# 4th_main.net
KiCad netlist of a schematic drawn in Altium Designer
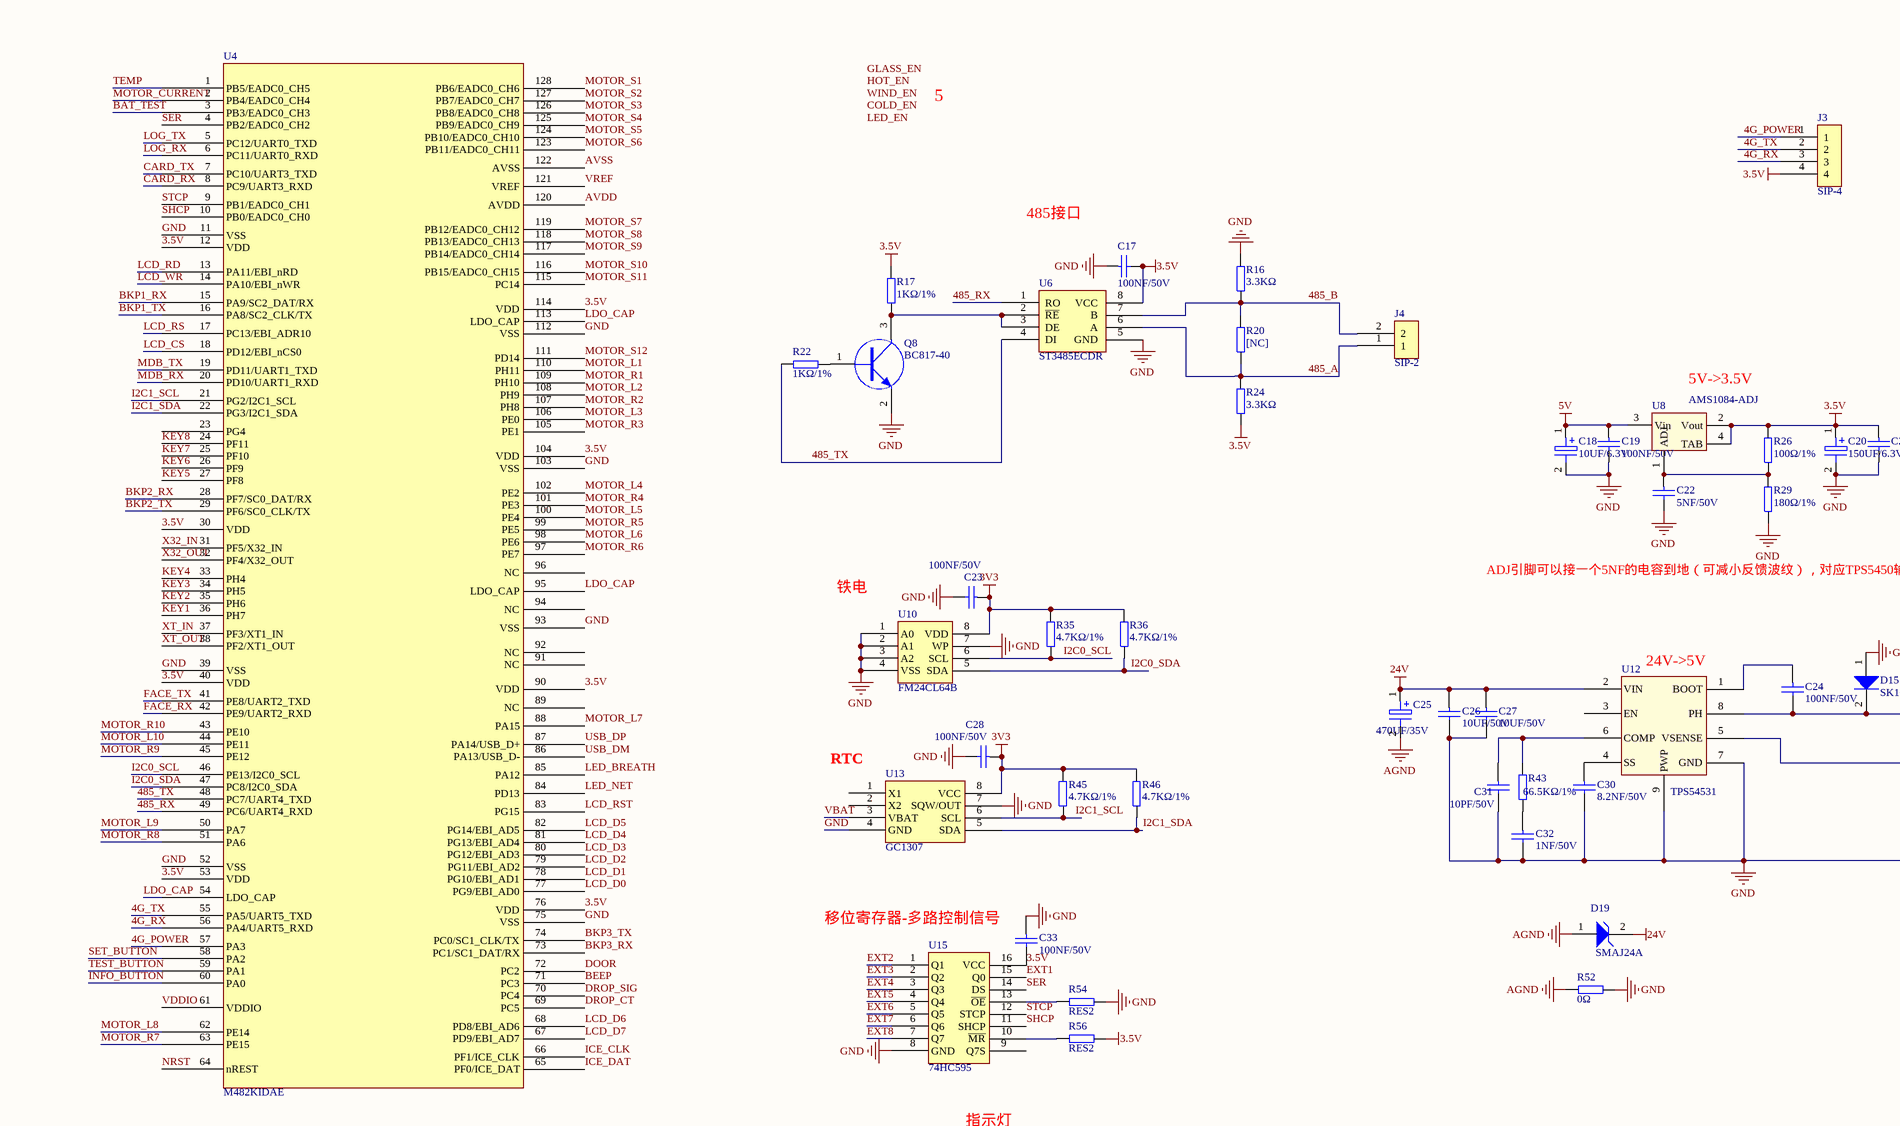
[diagram p0: 4th_main.SchDoc, top left]
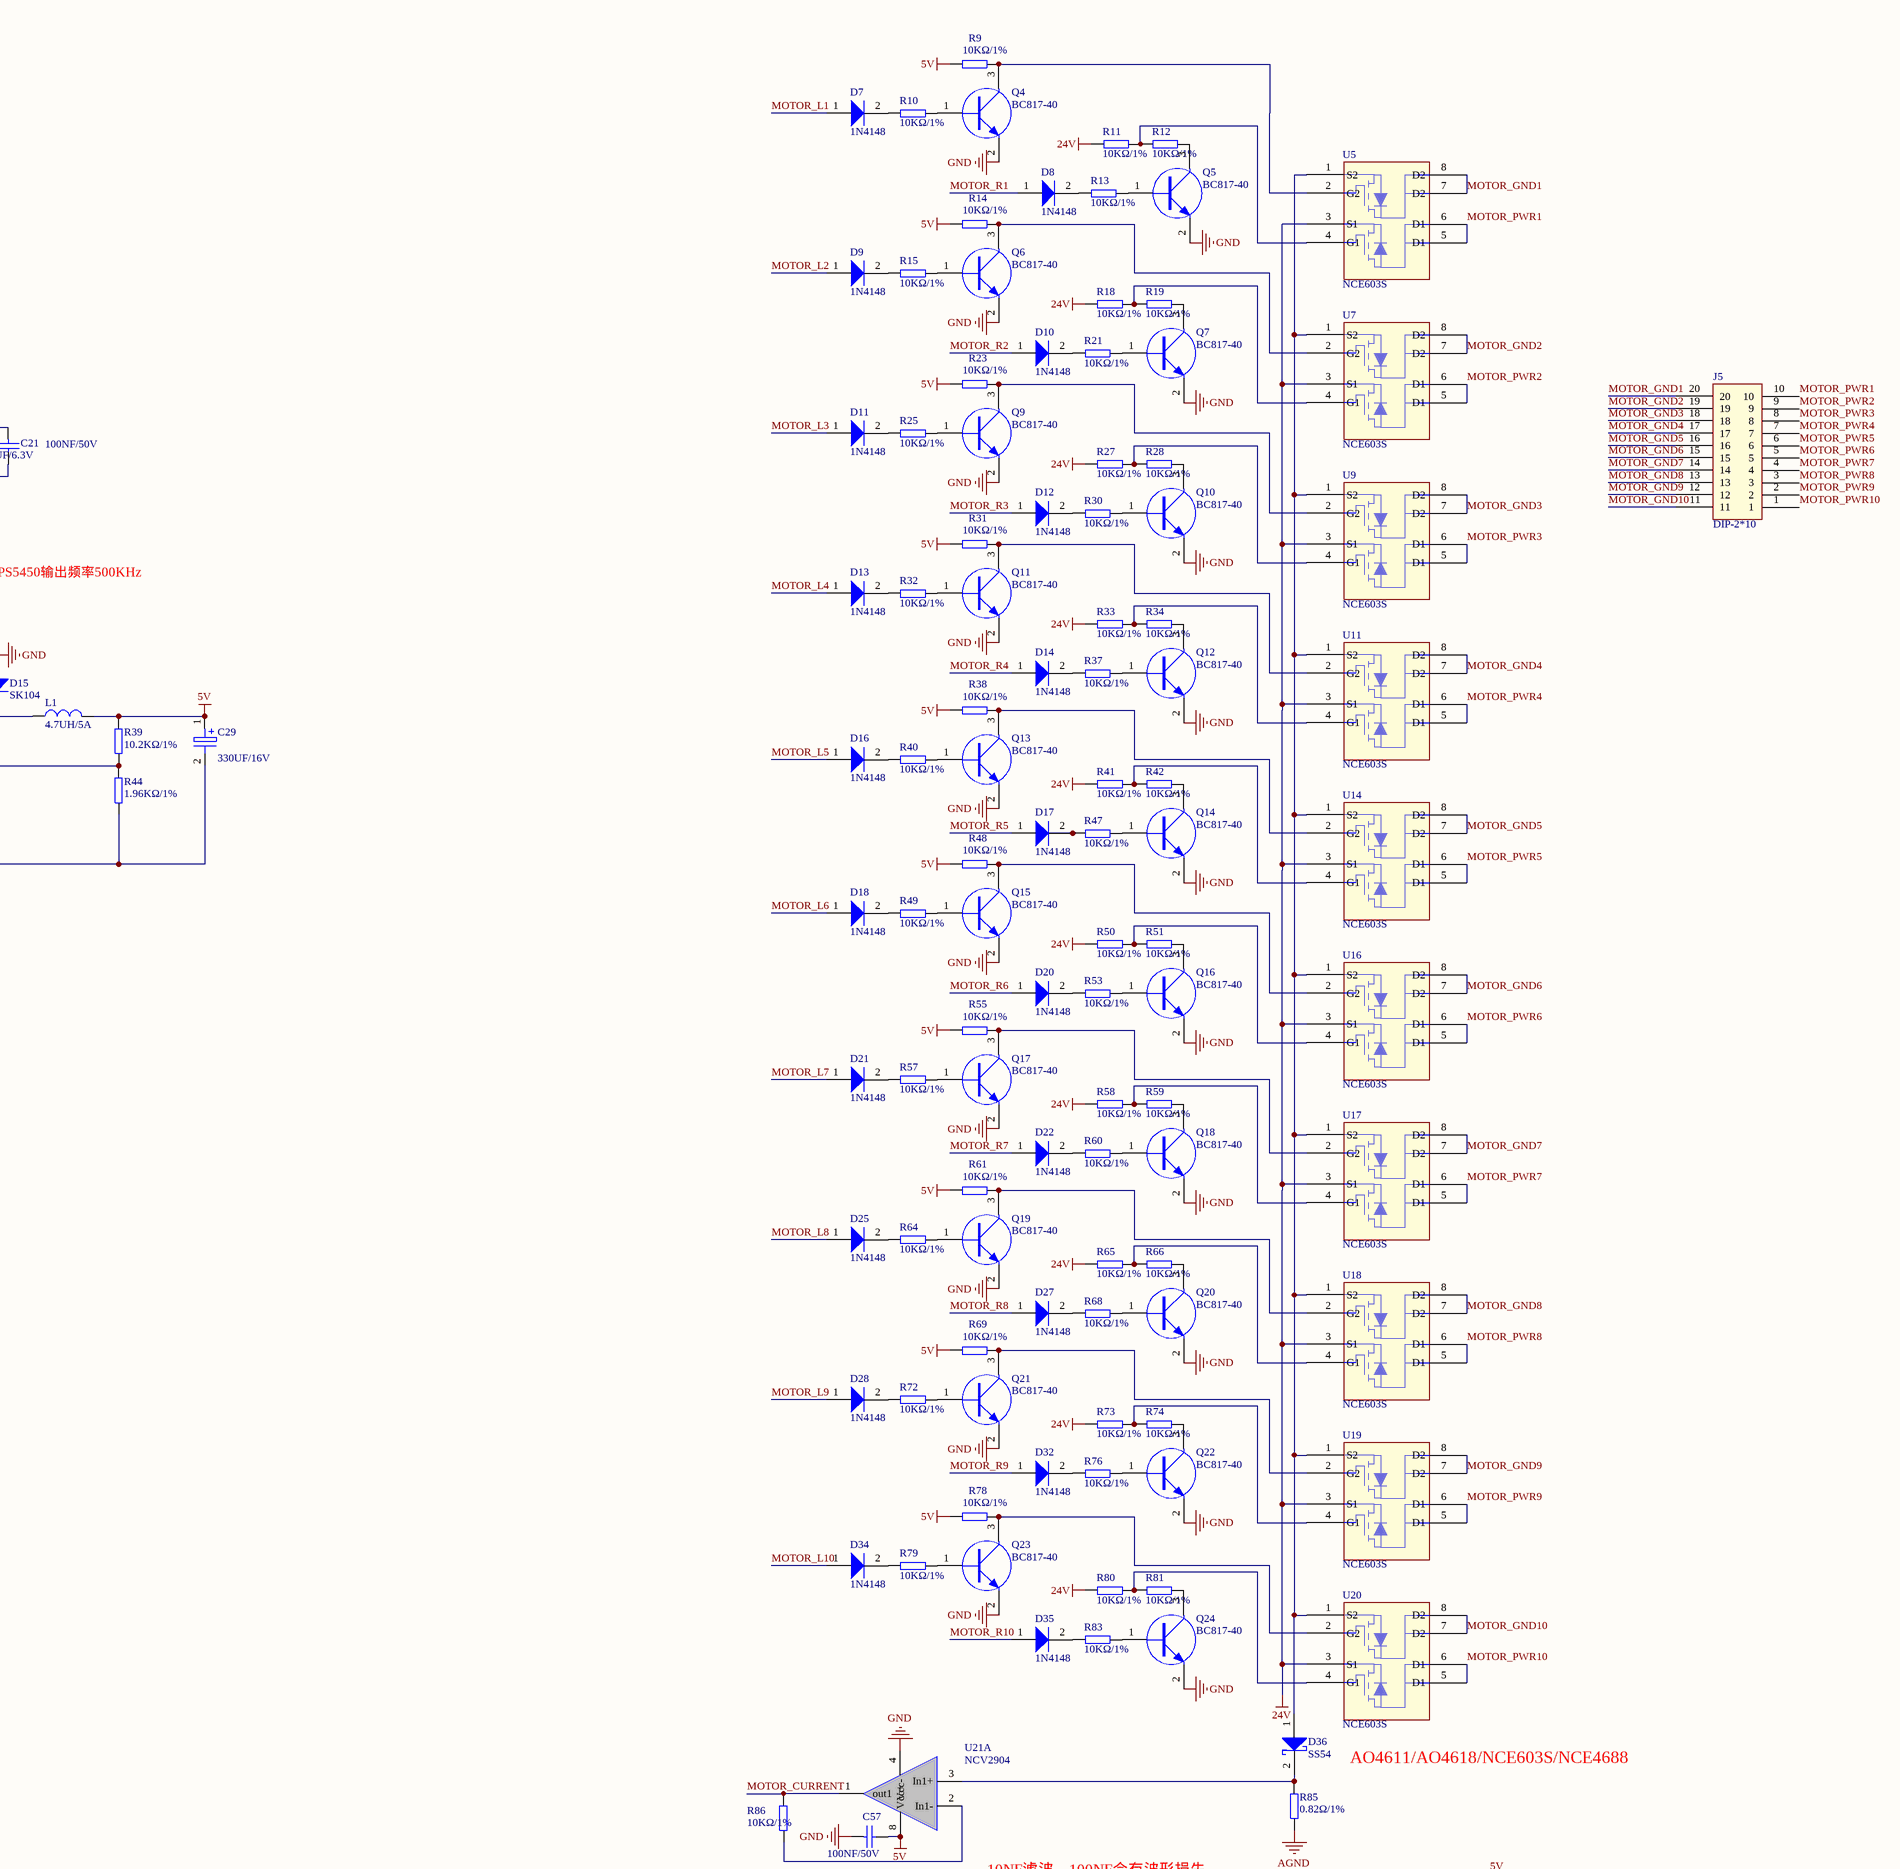
[diagram p1: 4th_main.SchDoc, top right]
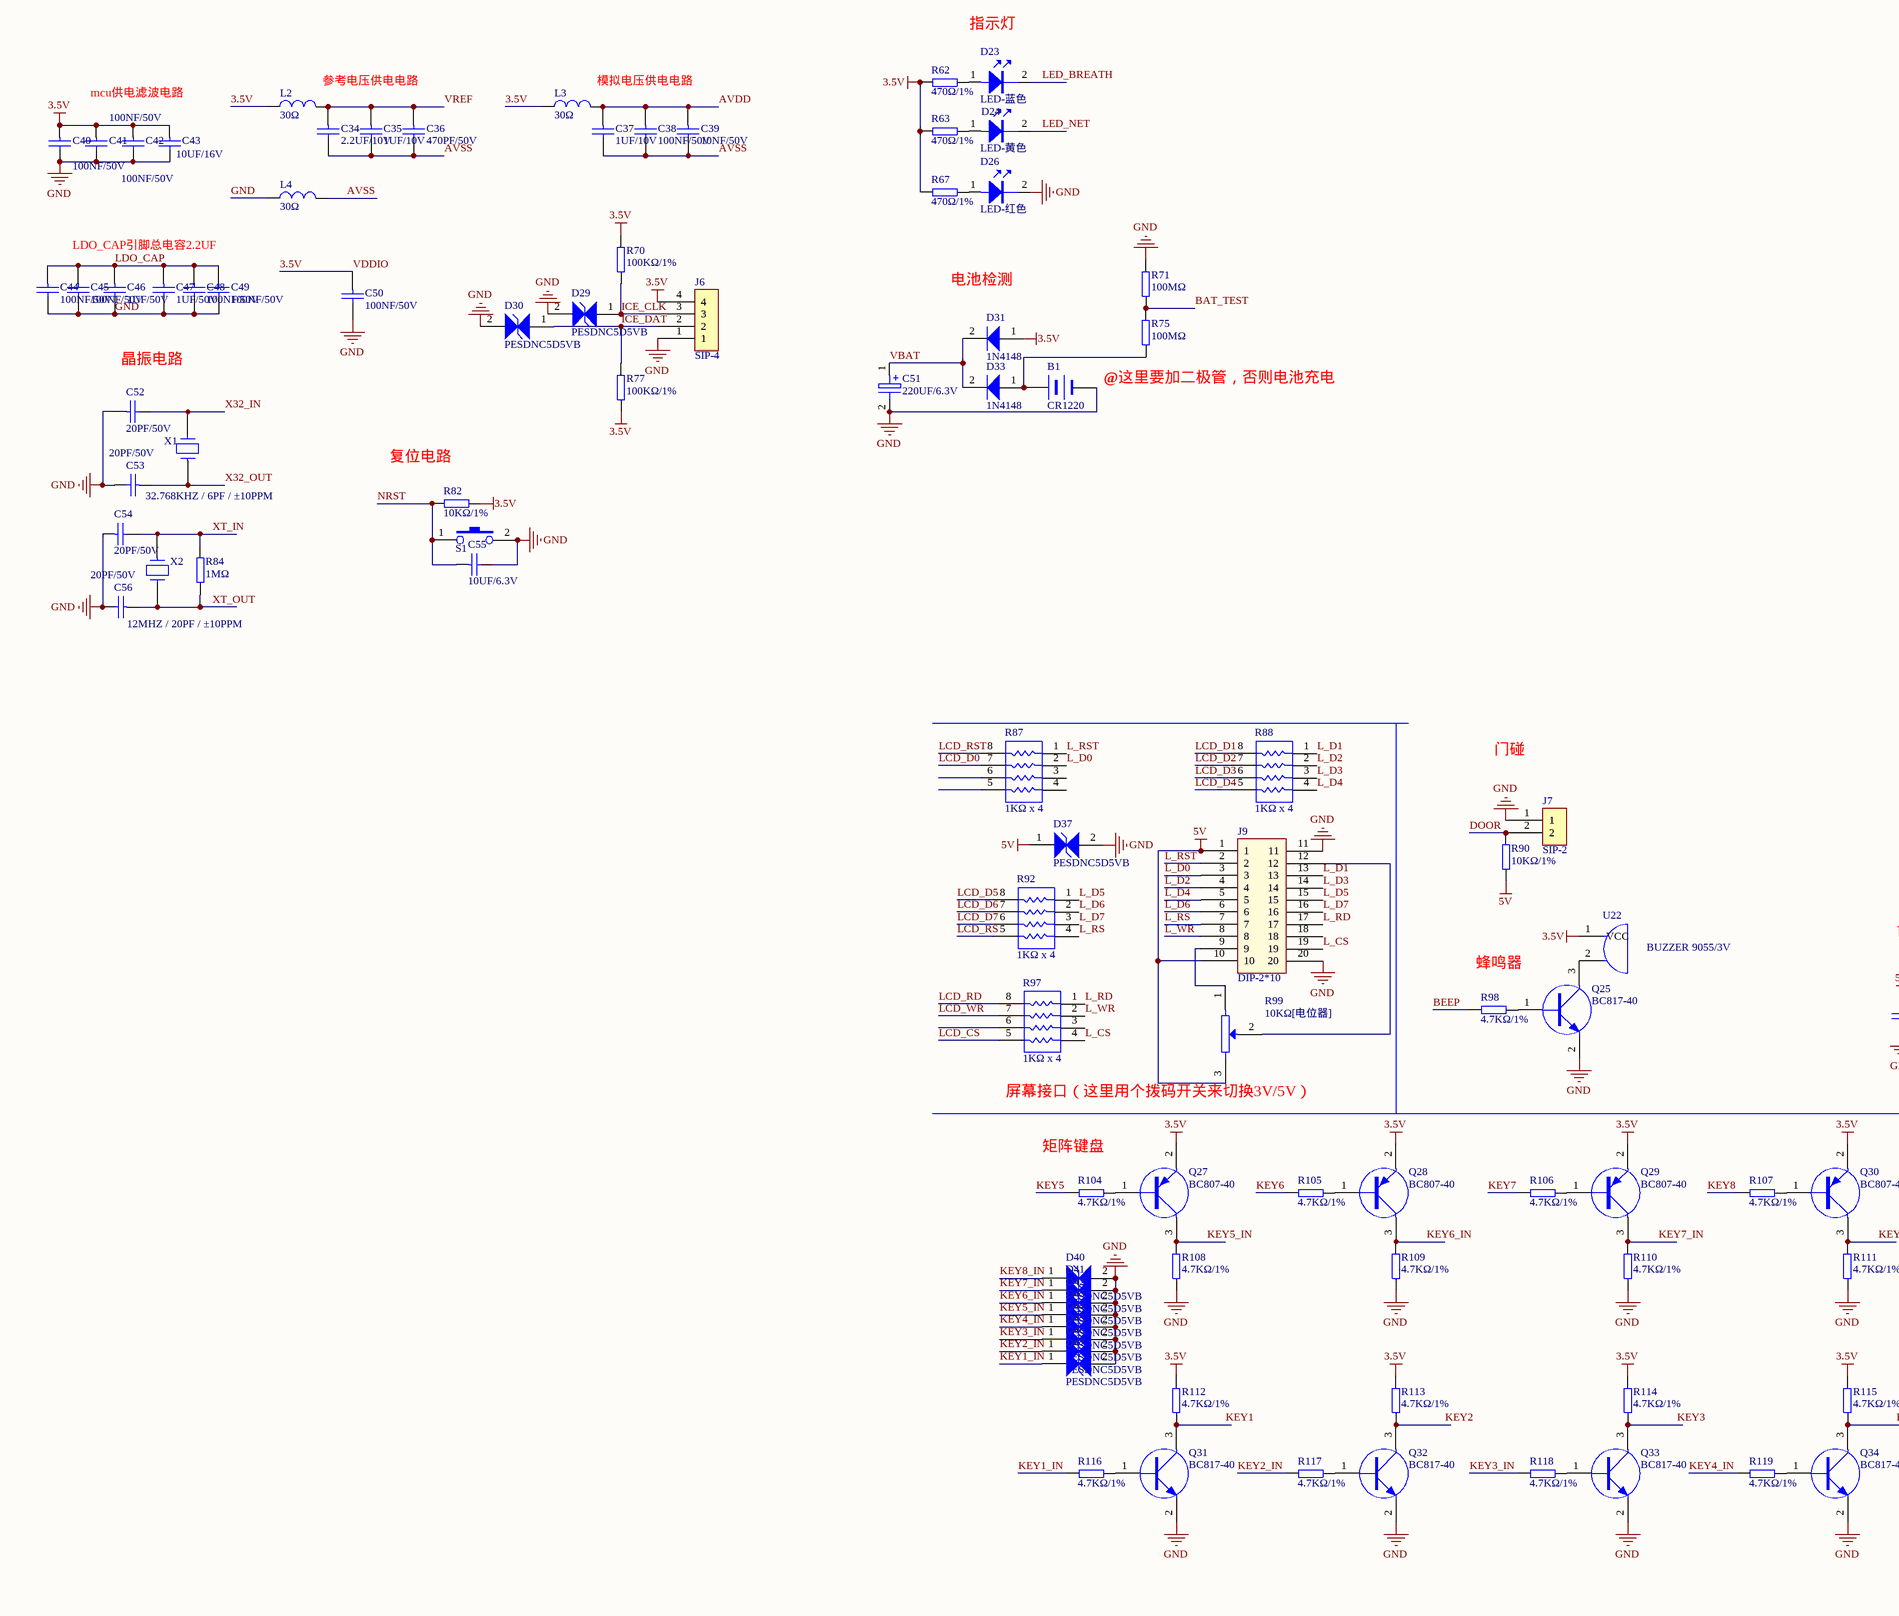
[diagram p2: 4th_main.SchDoc, bottom left]
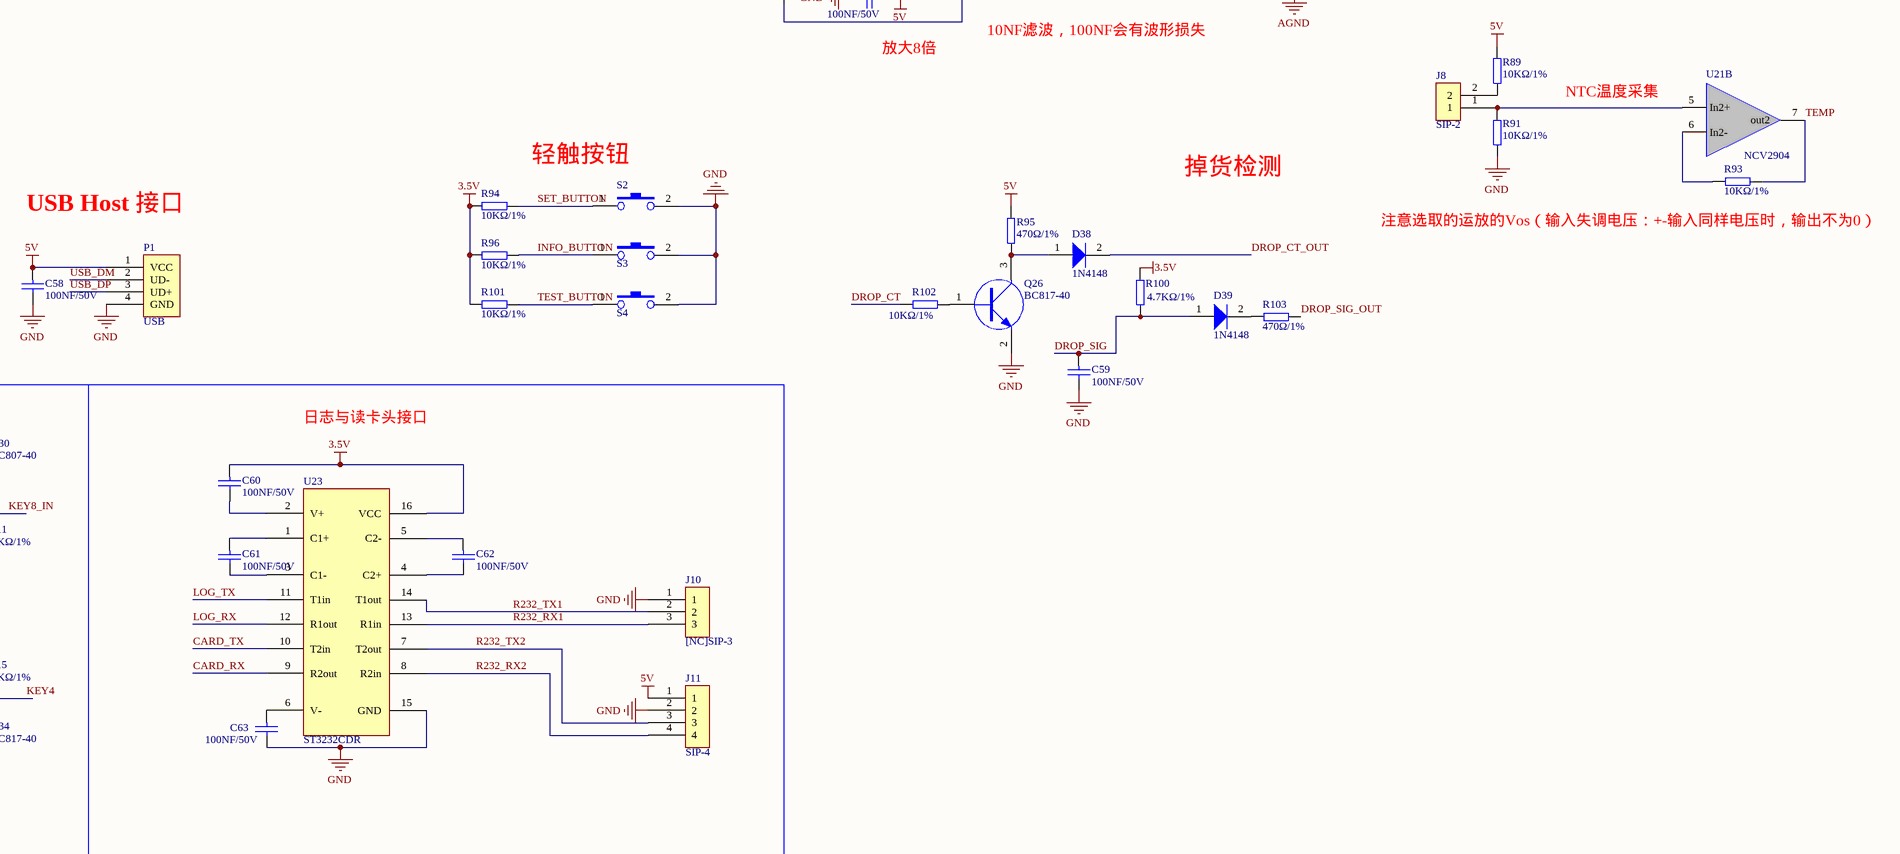
[diagram p3: 4th_main.SchDoc, bottom right]

(export (version "E")
  (design (tool "Eeschema 10.0.6"))
  (components
    (comp (ref "B1")
      (value "CR1220")
      (footprint "CR1220")
      (description "电池座")
      (libsource (lib "红牛板Schlib") (part "BATTERY"))
    )
    (comp (ref "C17")
      (value "100NF/50V")
      (footprint "0603_C")
      (description "无极性电容")
      (libsource (lib "Integrated_Library") (part "CAP"))
    )
    (comp (ref "C18")
      (value "10UF/6.3V")
      (footprint "CASE-A_3216")
      (description "钽电容")
      (libsource (lib "Integrated_Library") (part "CAP POLAR"))
    )
    (comp (ref "C19")
      (value "100NF/50V")
      (footprint "0603_C")
      (description "无极性电容")
      (libsource (lib "Integrated_Library") (part "CAP"))
    )
    (comp (ref "C20")
      (value "150UF/6.3V")
      (footprint "CASE-B_3528")
      (description "极性电容")
      (libsource (lib "Integrated_Library") (part "CAP POLAR"))
    )
    (comp (ref "C21")
      (value "100NF/50V")
      (footprint "0603_C")
      (description "无极性电容")
      (libsource (lib "Integrated_Library") (part "CAP"))
    )
    (comp (ref "C22")
      (value "5NF/50V")
      (footprint "0603_C")
      (description "无极性电容")
      (libsource (lib "Integrated_Library") (part "CAP"))
    )
    (comp (ref "C23")
      (value "100NF/50V")
      (footprint "0603_C")
      (description "无极性电容")
      (libsource (lib "Integrated_Library") (part "CAP"))
    )
    (comp (ref "C24")
      (value "100NF/50V")
      (footprint "0603_C")
      (description "无极性电容")
      (libsource (lib "") (part "CAP_1"))
    )
    (comp (ref "C25")
      (value "470UF/35V")
      (footprint "CAP-TH_BD10.0-P5.00-D1.0-FD")
      (description "电解电容")
      (libsource (lib "Integrated_Library") (part "CAP POLAR"))
    )
    (comp (ref "C26")
      (value "10UF/50V")
      (footprint "1206_C")
      (description "无极性电容")
      (libsource (lib "") (part "CAP_1"))
    )
    (comp (ref "C27")
      (value "10UF/50V")
      (footprint "1206_C")
      (description "无极性电容")
      (libsource (lib "") (part "CAP_1"))
    )
    (comp (ref "C28")
      (value "100NF/50V")
      (footprint "0603_C")
      (description "无极性电容")
      (libsource (lib "Integrated_Library") (part "CAP"))
    )
    (comp (ref "C29")
      (value "330UF/16V")
      (footprint "CAP-TH_BD8.0-P3.50-D1.0-FD")
      (description "直插电解电容")
      (libsource (lib "Integrated_Library") (part "CAP POLAR"))
    )
    (comp (ref "C30")
      (value "8.2NF/50V")
      (footprint "0603_C")
      (description "无极性电容")
      (libsource (lib "") (part "CAP_1"))
    )
    (comp (ref "C31")
      (value "10PF/50V")
      (footprint "0603_C")
      (description "无极性电容")
      (libsource (lib "") (part "CAP_1"))
    )
    (comp (ref "C32")
      (value "1NF/50V")
      (footprint "0603_C")
      (description "无极性电容")
      (libsource (lib "") (part "CAP_1"))
    )
    (comp (ref "C33")
      (value "100NF/50V")
      (footprint "0603_C")
      (description "无极性电容")
      (libsource (lib "") (part "CAP_1"))
    )
    (comp (ref "C34")
      (value "2.2UF/10V")
      (footprint "0603_C")
      (description "无极性电容")
      (libsource (lib "") (part "CAP_1"))
    )
    (comp (ref "C35")
      (value "1UF/10V")
      (footprint "0603_C")
      (description "无极性电容")
      (libsource (lib "") (part "CAP_1"))
    )
    (comp (ref "C36")
      (value "470PF/50V")
      (footprint "0603_C")
      (description "无极性电容")
      (libsource (lib "") (part "CAP_1"))
    )
    (comp (ref "C37")
      (value "1UF/10V")
      (footprint "0603_C")
      (description "无极性电容")
      (libsource (lib "") (part "CAP_1"))
    )
    (comp (ref "C38")
      (value "100NF/50V")
      (footprint "0603_C")
      (description "无极性电容")
      (libsource (lib "") (part "CAP_1"))
    )
    (comp (ref "C39")
      (value "10NF/50V")
      (footprint "0603_C")
      (description "无极性电容")
      (libsource (lib "") (part "CAP_1"))
    )
    (comp (ref "C40")
      (value "100NF/50V")
      (footprint "0603_C")
      (description "无极性电容")
      (libsource (lib "Integrated_Library") (part "CAP"))
    )
    (comp (ref "C41")
      (value "100NF/50V")
      (footprint "0603_C")
      (description "无极性电容")
      (libsource (lib "Integrated_Library") (part "CAP"))
    )
    (comp (ref "C42")
      (value "100NF/50V")
      (footprint "0603_C")
      (description "无极性电容")
      (libsource (lib "Integrated_Library") (part "CAP"))
    )
    (comp (ref "C43")
      (value "10UF/16V")
      (footprint "0603_C")
      (description "无极性电容")
      (libsource (lib "Integrated_Library") (part "CAP"))
    )
    (comp (ref "C44")
      (value "100NF/50V")
      (footprint "0603_C")
      (description "无极性电容")
      (libsource (lib "") (part "CAP_1"))
    )
    (comp (ref "C45")
      (value "100NF/50V")
      (footprint "0603_C")
      (description "无极性电容")
      (libsource (lib "") (part "CAP_1"))
    )
    (comp (ref "C46")
      (value "1UF/50V")
      (footprint "0603_C")
      (description "无极性电容")
      (libsource (lib "") (part "CAP_1"))
    )
    (comp (ref "C47")
      (value "1UF/50V")
      (footprint "0603_C")
      (description "无极性电容")
      (libsource (lib "") (part "CAP_1"))
    )
    (comp (ref "C48")
      (value "100NF/50V")
      (footprint "0603_C")
      (description "无极性电容")
      (libsource (lib "") (part "CAP_1"))
    )
    (comp (ref "C49")
      (value "100NF/50V")
      (footprint "0603_C")
      (description "无极性电容")
      (libsource (lib "") (part "CAP_1"))
    )
    (comp (ref "C50")
      (value "100NF/50V")
      (footprint "0603_C")
      (description "无极性电容")
      (libsource (lib "") (part "CAP_1"))
    )
    (comp (ref "C51")
      (value "220UF/6.3V")
      (footprint "CASE-B_3528")
      (description "钽电容")
      (libsource (lib "Integrated_Library") (part "CAP POLAR"))
    )
    (comp (ref "C52")
      (value "20PF/50V")
      (footprint "0603_C")
      (description "无极性电容")
      (libsource (lib "Integrated_Library") (part "CAP"))
    )
    (comp (ref "C53")
      (value "20PF/50V")
      (footprint "0603_C")
      (description "无极性电容")
      (libsource (lib "Integrated_Library") (part "CAP"))
    )
    (comp (ref "C54")
      (value "20PF/50V")
      (footprint "0603_C")
      (description "无极性电容")
      (libsource (lib "Integrated_Library") (part "CAP"))
    )
    (comp (ref "C55")
      (value "10UF/6.3V")
      (footprint "0603_C")
      (description "无极性电容")
      (libsource (lib "Integrated_Library") (part "CAP"))
    )
    (comp (ref "C56")
      (value "20PF/50V")
      (footprint "0603_C")
      (description "无极性电容")
      (libsource (lib "Integrated_Library") (part "CAP"))
    )
    (comp (ref "C57")
      (value "100NF/50V")
      (footprint "0603_C")
      (description "无极性电容")
      (libsource (lib "Integrated_Library") (part "CAP"))
    )
    (comp (ref "C58")
      (value "100NF/50V")
      (footprint "0603_C")
      (description "无极性电容")
      (libsource (lib "Integrated_Library") (part "CAP"))
    )
    (comp (ref "C59")
      (value "100NF/50V")
      (footprint "0603_C")
      (description "无极性电容")
      (libsource (lib "Integrated_Library") (part "CAP"))
    )
    (comp (ref "C60")
      (value "100NF/50V")
      (footprint "0603_C")
      (description "无极性电容")
      (libsource (lib "Integrated_Library") (part "CAP"))
    )
    (comp (ref "C61")
      (value "100NF/50V")
      (footprint "0603_C")
      (description "无极性电容")
      (libsource (lib "Integrated_Library") (part "CAP"))
    )
    (comp (ref "C62")
      (value "100NF/50V")
      (footprint "0603_C")
      (description "无极性电容")
      (libsource (lib "Integrated_Library") (part "CAP"))
    )
    (comp (ref "C63")
      (value "100NF/50V")
      (footprint "0603_C")
      (description "无极性电容")
      (libsource (lib "Integrated_Library") (part "CAP"))
    )
    (comp (ref "D7")
      (value "1N4148")
      (footprint "SOD-123_L2.8-W1.8-LS3.7-RD")
      (description "二极管")
      (libsource (lib "Integrated_Library") (part "Diodes"))
    )
    (comp (ref "D8")
      (value "1N4148")
      (footprint "SOD-123_L2.8-W1.8-LS3.7-RD")
      (description "高速开关二极管")
      (libsource (lib "Integrated_Library") (part "1N4148"))
    )
    (comp (ref "D9")
      (value "1N4148")
      (footprint "SOD-123_L2.8-W1.8-LS3.7-RD")
      (description "二极管")
      (libsource (lib "Integrated_Library") (part "Diodes"))
    )
    (comp (ref "D10")
      (value "1N4148")
      (footprint "SOD-123_L2.8-W1.8-LS3.7-RD")
      (description "高速开关二极管")
      (libsource (lib "Integrated_Library") (part "1N4148"))
    )
    (comp (ref "D11")
      (value "1N4148")
      (footprint "SOD-123_L2.8-W1.8-LS3.7-RD")
      (description "二极管")
      (libsource (lib "Integrated_Library") (part "Diodes"))
    )
    (comp (ref "D12")
      (value "1N4148")
      (footprint "SOD-123_L2.8-W1.8-LS3.7-RD")
      (description "高速开关二极管")
      (libsource (lib "Integrated_Library") (part "1N4148"))
    )
    (comp (ref "D13")
      (value "1N4148")
      (footprint "SOD-123_L2.8-W1.8-LS3.7-RD")
      (description "二极管")
      (libsource (lib "Integrated_Library") (part "Diodes"))
    )
    (comp (ref "D14")
      (value "1N4148")
      (footprint "SOD-123_L2.8-W1.8-LS3.7-RD")
      (description "高速开关二极管")
      (libsource (lib "Integrated_Library") (part "1N4148"))
    )
    (comp (ref "D15")
      (value "SK104")
      (footprint "SMC/DO214AB")
      (description "肖特基二极管/10A")
      (libsource (lib "Integrated_Library") (part "Diodes"))
    )
    (comp (ref "D16")
      (value "1N4148")
      (footprint "SOD-123_L2.8-W1.8-LS3.7-RD")
      (description "二极管")
      (libsource (lib "Integrated_Library") (part "Diodes"))
    )
    (comp (ref "D17")
      (value "1N4148")
      (footprint "SOD-123_L2.8-W1.8-LS3.7-RD")
      (description "高速开关二极管")
      (libsource (lib "Integrated_Library") (part "1N4148"))
    )
    (comp (ref "D18")
      (value "1N4148")
      (footprint "SOD-123_L2.8-W1.8-LS3.7-RD")
      (description "二极管")
      (libsource (lib "Integrated_Library") (part "Diodes"))
    )
    (comp (ref "D19")
      (value "SMAJ24A")
      (footprint "SMA/DO214AC")
      (description "稳压二极管")
      (fields (field (name "PUBLISHER") "Altium Limited"))
      (libsource (lib "Integrated_Library") (part "Zener diode"))
    )
    (comp (ref "D20")
      (value "1N4148")
      (footprint "SOD-123_L2.8-W1.8-LS3.7-RD")
      (description "高速开关二极管")
      (libsource (lib "Integrated_Library") (part "1N4148"))
    )
    (comp (ref "D21")
      (value "1N4148")
      (footprint "SOD-123_L2.8-W1.8-LS3.7-RD")
      (description "二极管")
      (libsource (lib "Integrated_Library") (part "Diodes"))
    )
    (comp (ref "D22")
      (value "1N4148")
      (footprint "SOD-123_L2.8-W1.8-LS3.7-RD")
      (description "高速开关二极管")
      (libsource (lib "Integrated_Library") (part "1N4148"))
    )
    (comp (ref "D23")
      (value "LED-蓝色")
      (footprint "0603_D")
      (description "发光二极管")
      (libsource (lib "Integrated_Library") (part "LED"))
    )
    (comp (ref "D24")
      (value "LED-黄色")
      (footprint "0603_D")
      (description "发光二极管")
      (libsource (lib "Integrated_Library") (part "LED"))
    )
    (comp (ref "D25")
      (value "1N4148")
      (footprint "SOD-123_L2.8-W1.8-LS3.7-RD")
      (description "二极管")
      (libsource (lib "Integrated_Library") (part "Diodes"))
    )
    (comp (ref "D26")
      (value "LED-红色")
      (footprint "0603_D")
      (description "发光二极管")
      (libsource (lib "Integrated_Library") (part "LED"))
    )
    (comp (ref "D27")
      (value "1N4148")
      (footprint "SOD-123_L2.8-W1.8-LS3.7-RD")
      (description "高速开关二极管")
      (libsource (lib "Integrated_Library") (part "1N4148"))
    )
    (comp (ref "D28")
      (value "1N4148")
      (footprint "SOD-123_L2.8-W1.8-LS3.7-RD")
      (description "二极管")
      (libsource (lib "Integrated_Library") (part "Diodes"))
    )
    (comp (ref "D29")
      (value "PESDNC5D5VB")
      (footprint "SOD-523")
      (description "TVS 瞬态抑制二极管")
      (fields (field (name "PUBLISHER") "Altium Limited"))
      (libsource (lib "Integrated_Library") (part "TVS"))
    )
    (comp (ref "D30")
      (value "PESDNC5D5VB")
      (footprint "SOD-523")
      (description "TVS 瞬态抑制二极管")
      (fields (field (name "PUBLISHER") "Altium Limited"))
      (libsource (lib "Integrated_Library") (part "TVS"))
    )
    (comp (ref "D31")
      (value "1N4148")
      (footprint "LL34_2P")
      (description "高速开关二极管")
      (libsource (lib "Integrated_Library") (part "1N4148"))
    )
    (comp (ref "D32")
      (value "1N4148")
      (footprint "SOD-123_L2.8-W1.8-LS3.7-RD")
      (description "高速开关二极管")
      (libsource (lib "Integrated_Library") (part "1N4148"))
    )
    (comp (ref "D33")
      (value "1N4148")
      (footprint "LL34_2P")
      (description "高速开关二极管")
      (libsource (lib "Integrated_Library") (part "1N4148"))
    )
    (comp (ref "D34")
      (value "1N4148")
      (footprint "SOD-123_L2.8-W1.8-LS3.7-RD")
      (description "二极管")
      (libsource (lib "Integrated_Library") (part "Diodes"))
    )
    (comp (ref "D35")
      (value "1N4148")
      (footprint "SOD-123_L2.8-W1.8-LS3.7-RD")
      (description "高速开关二极管")
      (libsource (lib "Integrated_Library") (part "1N4148"))
    )
    (comp (ref "D36")
      (value "SS54")
      (footprint "SMA/DO214AC")
      (description "肖特基二极管")
      (fields (field (name "PUBLISHER") "Altium Limited"))
      (libsource (lib "Integrated_Library") (part "SS54"))
    )
    (comp (ref "D37")
      (value "PESDNC5D5VB")
      (footprint "SOD-523")
      (description "TVS 瞬态抑制二极管")
      (fields (field (name "PUBLISHER") "Altium Limited"))
      (libsource (lib "Integrated_Library") (part "TVS"))
    )
    (comp (ref "D38")
      (value "1N4148")
      (footprint "SOD-123_L2.8-W1.8-LS3.7-RD")
      (description "高速开关二极管")
      (libsource (lib "Integrated_Library") (part "1N4148"))
    )
    (comp (ref "D39")
      (value "1N4148")
      (footprint "SOD-123_L2.8-W1.8-LS3.7-RD")
      (description "高速开关二极管")
      (libsource (lib "Integrated_Library") (part "1N4148"))
    )
    (comp (ref "D40")
      (value "PESDNC5D5VB")
      (footprint "SOD-523")
      (description "TVS 瞬态抑制二极管")
      (fields (field (name "PUBLISHER") "Altium Limited"))
      (libsource (lib "Integrated_Library") (part "TVS"))
    )
    (comp (ref "D41")
      (value "PESDNC5D5VB")
      (footprint "SOD-523")
      (description "TVS 瞬态抑制二极管")
      (fields (field (name "PUBLISHER") "Altium Limited"))
      (libsource (lib "Integrated_Library") (part "TVS"))
    )
    (comp (ref "D42")
      (value "PESDNC5D5VB")
      (footprint "SOD-523")
      (description "TVS 瞬态抑制二极管")
      (fields (field (name "PUBLISHER") "Altium Limited"))
      (libsource (lib "Integrated_Library") (part "TVS"))
    )
    (comp (ref "D43")
      (value "PESDNC5D5VB")
      (footprint "SOD-523")
      (description "TVS 瞬态抑制二极管")
      (fields (field (name "PUBLISHER") "Altium Limited"))
      (libsource (lib "Integrated_Library") (part "TVS"))
    )
    (comp (ref "D44")
      (value "PESDNC5D5VB")
      (footprint "SOD-523")
      (description "TVS 瞬态抑制二极管")
      (fields (field (name "PUBLISHER") "Altium Limited"))
      (libsource (lib "Integrated_Library") (part "TVS"))
    )
    (comp (ref "D45")
      (value "PESDNC5D5VB")
      (footprint "SOD-523")
      (description "TVS 瞬态抑制二极管")
      (fields (field (name "PUBLISHER") "Altium Limited"))
      (libsource (lib "Integrated_Library") (part "TVS"))
    )
    (comp (ref "D46")
      (value "PESDNC5D5VB")
      (footprint "SOD-523")
      (description "TVS 瞬态抑制二极管")
      (fields (field (name "PUBLISHER") "Altium Limited"))
      (libsource (lib "Integrated_Library") (part "TVS"))
    )
    (comp (ref "D47")
      (value "PESDNC5D5VB")
      (footprint "SOD-523")
      (description "TVS 瞬态抑制二极管")
      (fields (field (name "PUBLISHER") "Altium Limited"))
      (libsource (lib "Integrated_Library") (part "TVS"))
    )
    (comp (ref "J3")
      (value "SIP-4")
      (footprint "XHB-4A")
      (description "单排4P插座")
      (libsource (lib "Integrated_Library") (part "SIP-4"))
    )
    (comp (ref "J4")
      (value "SIP-2")
      (footprint "PHS-2AW")
      (description "单排2P插座")
      (libsource (lib "Integrated_Library") (part "SIP-2"))
    )
    (comp (ref "J5")
      (value "DIP-2*10")
      (footprint "5557-2*10A")
      (description "双排2*10P插座")
      (libsource (lib "Integrated_Library") (part "DIP-2*10"))
    )
    (comp (ref "J6")
      (value "SIP-4")
      (footprint "XHB-4A")
      (description "单排4P插座")
      (libsource (lib "") (part "SIP-4_1"))
    )
    (comp (ref "J7")
      (value "SIP-2")
      (footprint "PHS-2AW")
      (description "单排2P插座")
      (libsource (lib "") (part "SIP-2_1"))
    )
    (comp (ref "J8")
      (value "SIP-2")
      (footprint "XHB-2A")
      (description "单排2P插座")
      (libsource (lib "") (part "SIP-2_2"))
    )
    (comp (ref "J9")
      (value "DIP-2*10")
      (footprint "PHB-2*10AW")
      (description "双排2*10P插座")
      (libsource (lib "") (part "DIP-2*10_1"))
    )
    (comp (ref "J10")
      (value "[NC]SIP-3")
      (footprint "XHB-3A")
      (description "单排3P插座")
      (libsource (lib "Integrated_Library") (part "SIP-3"))
    )
    (comp (ref "J11")
      (value "SIP-4")
      (footprint "PHS-4AW")
      (description "单排4P插座")
      (libsource (lib "Integrated_Library") (part "SIP-4"))
    )
    (comp (ref "L1")
      (value "4.7UH/5A")
      (footprint "IND-SMD_0630")
      (description "电感")
      (libsource (lib "Integrated_Library") (part "INDUCTOR"))
    )
    (comp (ref "L2")
      (value "30Ω")
      (footprint "0603_L")
      (description "电感")
      (libsource (lib "Integrated_Library") (part "INDUCTOR"))
    )
    (comp (ref "L3")
      (value "30Ω")
      (footprint "0603_L")
      (description "电感")
      (libsource (lib "Integrated_Library") (part "INDUCTOR"))
    )
    (comp (ref "L4")
      (value "30Ω")
      (footprint "0603_L")
      (description "电感")
      (libsource (lib "Integrated_Library") (part "INDUCTOR"))
    )
    (comp (ref "P1")
      (value "USB")
      (footprint "USB-180度-10mm超短")
      (description "USB座")
      (libsource (lib "Integrated_Library") (part "USB"))
    )
    (comp (ref "Q4")
      (value "BC817-40")
      (footprint "SOT-23-3")
      (description "NPN三极管")
      (libsource (lib "Integrated_Library") (part "BC817-40"))
    )
    (comp (ref "Q5")
      (value "BC817-40")
      (footprint "SOT-23-3")
      (description "NPN三极管")
      (libsource (lib "Integrated_Library") (part "BC817-40"))
    )
    (comp (ref "Q6")
      (value "BC817-40")
      (footprint "SOT-23-3")
      (description "NPN三极管")
      (libsource (lib "Integrated_Library") (part "BC817-40"))
    )
    (comp (ref "Q7")
      (value "BC817-40")
      (footprint "SOT-23-3")
      (description "NPN三极管")
      (libsource (lib "Integrated_Library") (part "BC817-40"))
    )
    (comp (ref "Q8")
      (value "BC817-40")
      (footprint "SOT-23-3")
      (description "NPN")
      (libsource (lib "Integrated_Library") (part "S8050"))
    )
    (comp (ref "Q9")
      (value "BC817-40")
      (footprint "SOT-23-3")
      (description "NPN三极管")
      (libsource (lib "Integrated_Library") (part "BC817-40"))
    )
    (comp (ref "Q10")
      (value "BC817-40")
      (footprint "SOT-23-3")
      (description "NPN三极管")
      (libsource (lib "Integrated_Library") (part "BC817-40"))
    )
    (comp (ref "Q11")
      (value "BC817-40")
      (footprint "SOT-23-3")
      (description "NPN三极管")
      (libsource (lib "Integrated_Library") (part "BC817-40"))
    )
    (comp (ref "Q12")
      (value "BC817-40")
      (footprint "SOT-23-3")
      (description "NPN三极管")
      (libsource (lib "Integrated_Library") (part "BC817-40"))
    )
    (comp (ref "Q13")
      (value "BC817-40")
      (footprint "SOT-23-3")
      (description "NPN三极管")
      (libsource (lib "Integrated_Library") (part "BC817-40"))
    )
    (comp (ref "Q14")
      (value "BC817-40")
      (footprint "SOT-23-3")
      (description "NPN三极管")
      (libsource (lib "Integrated_Library") (part "BC817-40"))
    )
    (comp (ref "Q15")
      (value "BC817-40")
      (footprint "SOT-23-3")
      (description "NPN三极管")
      (libsource (lib "Integrated_Library") (part "BC817-40"))
    )
    (comp (ref "Q16")
      (value "BC817-40")
      (footprint "SOT-23-3")
      (description "NPN三极管")
      (libsource (lib "Integrated_Library") (part "BC817-40"))
    )
    (comp (ref "Q17")
      (value "BC817-40")
      (footprint "SOT-23-3")
      (description "NPN三极管")
      (libsource (lib "Integrated_Library") (part "BC817-40"))
    )
    (comp (ref "Q18")
      (value "BC817-40")
      (footprint "SOT-23-3")
      (description "NPN三极管")
      (libsource (lib "Integrated_Library") (part "BC817-40"))
    )
    (comp (ref "Q19")
      (value "BC817-40")
      (footprint "SOT-23-3")
      (description "NPN三极管")
      (libsource (lib "Integrated_Library") (part "BC817-40"))
    )
    (comp (ref "Q20")
      (value "BC817-40")
      (footprint "SOT-23-3")
      (description "NPN三极管")
      (libsource (lib "Integrated_Library") (part "BC817-40"))
    )
    (comp (ref "Q21")
      (value "BC817-40")
      (footprint "SOT-23-3")
      (description "NPN三极管")
      (libsource (lib "Integrated_Library") (part "BC817-40"))
    )
    (comp (ref "Q22")
      (value "BC817-40")
      (footprint "SOT-23-3")
      (description "NPN三极管")
      (libsource (lib "Integrated_Library") (part "BC817-40"))
    )
    (comp (ref "Q23")
      (value "BC817-40")
      (footprint "SOT-23-3")
      (description "NPN三极管")
      (libsource (lib "Integrated_Library") (part "BC817-40"))
    )
    (comp (ref "Q24")
      (value "BC817-40")
      (footprint "SOT-23-3")
      (description "NPN三极管")
      (libsource (lib "Integrated_Library") (part "BC817-40"))
    )
    (comp (ref "Q25")
      (value "BC817-40")
      (footprint "SOT-23-3")
      (description "NPN")
      (libsource (lib "Integrated_Library") (part "S8050"))
    )
    (comp (ref "Q26")
      (value "BC817-40")
      (footprint "SOT-23-3")
      (description "NPN三极管")
      (libsource (lib "Integrated_Library") (part "BC817-40"))
    )
    (comp (ref "Q27")
      (value "BC807-40")
      (footprint "SOT-23-3")
      (description "PNP")
      (libsource (lib "Integrated_Library") (part "S8550"))
    )
    (comp (ref "Q28")
      (value "BC807-40")
      (footprint "SOT-23-3")
      (description "PNP")
      (libsource (lib "Integrated_Library") (part "S8550"))
    )
    (comp (ref "Q29")
      (value "BC807-40")
      (footprint "SOT-23-3")
      (description "PNP")
      (libsource (lib "Integrated_Library") (part "S8550"))
    )
    (comp (ref "Q30")
      (value "BC807-40")
      (footprint "SOT-23-3")
      (description "PNP")
      (libsource (lib "Integrated_Library") (part "S8550"))
    )
    (comp (ref "Q31")
      (value "BC817-40")
      (footprint "SOT-23-3")
      (description "NPN")
      (libsource (lib "Integrated_Library") (part "S8050"))
    )
    (comp (ref "Q32")
      (value "BC817-40")
      (footprint "SOT-23-3")
      (description "NPN")
      (libsource (lib "Integrated_Library") (part "S8050"))
    )
    (comp (ref "Q33")
      (value "BC817-40")
      (footprint "SOT-23-3")
      (description "NPN")
      (libsource (lib "Integrated_Library") (part "S8050"))
    )
    (comp (ref "Q34")
      (value "BC817-40")
      (footprint "SOT-23-3")
      (description "NPN")
      (libsource (lib "Integrated_Library") (part "S8050"))
    )
    (comp (ref "R9")
      (value "10KΩ/1%")
      (footprint "0603_R")
      (description "电阻")
      (libsource (lib "Integrated_Library") (part "RES2"))
    )
    (comp (ref "R10")
      (value "10KΩ/1%")
      (footprint "0603_R")
      (description "电阻")
      (libsource (lib "Integrated_Library") (part "RES2"))
    )
    (comp (ref "R11")
      (value "10KΩ/1%")
      (footprint "0603_R")
      (description "电阻")
      (libsource (lib "Integrated_Library") (part "RES2"))
    )
    (comp (ref "R12")
      (value "10KΩ/1%")
      (footprint "0603_R")
      (description "电阻")
      (libsource (lib "Integrated_Library") (part "RES2"))
    )
    (comp (ref "R13")
      (value "10KΩ/1%")
      (footprint "0603_R")
      (description "电阻")
      (libsource (lib "Integrated_Library") (part "RES2"))
    )
    (comp (ref "R14")
      (value "10KΩ/1%")
      (footprint "0603_R")
      (description "电阻")
      (libsource (lib "Integrated_Library") (part "RES2"))
    )
    (comp (ref "R15")
      (value "10KΩ/1%")
      (footprint "0603_R")
      (description "电阻")
      (libsource (lib "Integrated_Library") (part "RES2"))
    )
    (comp (ref "R16")
      (value "3.3KΩ")
      (footprint "0603_R")
      (description "电阻")
      (libsource (lib "Integrated_Library") (part "RES2"))
    )
    (comp (ref "R17")
      (value "1KΩ/1%")
      (footprint "0603_R")
      (description "电阻")
      (libsource (lib "Integrated_Library") (part "RES2"))
    )
    (comp (ref "R18")
      (value "10KΩ/1%")
      (footprint "0603_R")
      (description "电阻")
      (libsource (lib "Integrated_Library") (part "RES2"))
    )
    (comp (ref "R19")
      (value "10KΩ/1%")
      (footprint "0603_R")
      (description "电阻")
      (libsource (lib "Integrated_Library") (part "RES2"))
    )
    (comp (ref "R20")
      (value "[NC]")
      (footprint "0603_R")
      (description "电阻")
      (libsource (lib "Integrated_Library") (part "RES2"))
    )
    (comp (ref "R21")
      (value "10KΩ/1%")
      (footprint "0603_R")
      (description "电阻")
      (libsource (lib "Integrated_Library") (part "RES2"))
    )
    (comp (ref "R22")
      (value "1KΩ/1%")
      (footprint "0603_R")
      (description "电阻")
      (libsource (lib "Integrated_Library") (part "RES2"))
    )
    (comp (ref "R23")
      (value "10KΩ/1%")
      (footprint "0603_R")
      (description "电阻")
      (libsource (lib "Integrated_Library") (part "RES2"))
    )
    (comp (ref "R24")
      (value "3.3KΩ")
      (footprint "0603_R")
      (description "电阻")
      (libsource (lib "Integrated_Library") (part "RES2"))
    )
    (comp (ref "R25")
      (value "10KΩ/1%")
      (footprint "0603_R")
      (description "电阻")
      (libsource (lib "Integrated_Library") (part "RES2"))
    )
    (comp (ref "R26")
      (value "100Ω/1%")
      (footprint "0603_R")
      (description "电阻")
      (libsource (lib "Integrated_Library") (part "RES2"))
    )
    (comp (ref "R27")
      (value "10KΩ/1%")
      (footprint "0603_R")
      (description "电阻")
      (libsource (lib "Integrated_Library") (part "RES2"))
    )
    (comp (ref "R28")
      (value "10KΩ/1%")
      (footprint "0603_R")
      (description "电阻")
      (libsource (lib "Integrated_Library") (part "RES2"))
    )
    (comp (ref "R29")
      (value "180Ω/1%")
      (footprint "0603_R")
      (description "电阻")
      (libsource (lib "Integrated_Library") (part "RES2"))
    )
    (comp (ref "R30")
      (value "10KΩ/1%")
      (footprint "0603_R")
      (description "电阻")
      (libsource (lib "Integrated_Library") (part "RES2"))
    )
    (comp (ref "R31")
      (value "10KΩ/1%")
      (footprint "0603_R")
      (description "电阻")
      (libsource (lib "Integrated_Library") (part "RES2"))
    )
    (comp (ref "R32")
      (value "10KΩ/1%")
      (footprint "0603_R")
      (description "电阻")
      (libsource (lib "Integrated_Library") (part "RES2"))
    )
    (comp (ref "R33")
      (value "10KΩ/1%")
      (footprint "0603_R")
      (description "电阻")
      (libsource (lib "Integrated_Library") (part "RES2"))
    )
    (comp (ref "R34")
      (value "10KΩ/1%")
      (footprint "0603_R")
      (description "电阻")
      (libsource (lib "Integrated_Library") (part "RES2"))
    )
    (comp (ref "R35")
      (value "4.7KΩ/1%")
      (footprint "0603_R")
      (description "电阻")
      (libsource (lib "Integrated_Library") (part "RES2"))
    )
    (comp (ref "R36")
      (value "4.7KΩ/1%")
      (footprint "0603_R")
      (description "电阻")
      (libsource (lib "Integrated_Library") (part "RES2"))
    )
    (comp (ref "R37")
      (value "10KΩ/1%")
      (footprint "0603_R")
      (description "电阻")
      (libsource (lib "Integrated_Library") (part "RES2"))
    )
    (comp (ref "R38")
      (value "10KΩ/1%")
      (footprint "0603_R")
      (description "电阻")
      (libsource (lib "Integrated_Library") (part "RES2"))
    )
    (comp (ref "R39")
      (value "10.2KΩ/1%")
      (footprint "0603_R")
      (description "电阻")
      (libsource (lib "Integrated_Library") (part "RES2"))
    )
    (comp (ref "R40")
      (value "10KΩ/1%")
      (footprint "0603_R")
      (description "电阻")
      (libsource (lib "Integrated_Library") (part "RES2"))
    )
    (comp (ref "R41")
      (value "10KΩ/1%")
      (footprint "0603_R")
      (description "电阻")
      (libsource (lib "Integrated_Library") (part "RES2"))
    )
    (comp (ref "R42")
      (value "10KΩ/1%")
      (footprint "0603_R")
      (description "电阻")
      (libsource (lib "Integrated_Library") (part "RES2"))
    )
    (comp (ref "R43")
      (value "66.5KΩ/1%")
      (footprint "0603_R")
      (description "电阻")
      (libsource (lib "Integrated_Library") (part "RES2"))
    )
    (comp (ref "R44")
      (value "1.96KΩ/1%")
      (footprint "0603_R")
      (description "电阻")
      (libsource (lib "Integrated_Library") (part "RES2"))
    )
    (comp (ref "R45")
      (value "4.7KΩ/1%")
      (footprint "0603_R")
      (description "电阻")
      (libsource (lib "Integrated_Library") (part "RES2"))
    )
    (comp (ref "R46")
      (value "4.7KΩ/1%")
      (footprint "0603_R")
      (description "电阻")
      (libsource (lib "Integrated_Library") (part "RES2"))
    )
    (comp (ref "R47")
      (value "10KΩ/1%")
      (footprint "0603_R")
      (description "电阻")
      (libsource (lib "Integrated_Library") (part "RES2"))
    )
    (comp (ref "R48")
      (value "10KΩ/1%")
      (footprint "0603_R")
      (description "电阻")
      (libsource (lib "Integrated_Library") (part "RES2"))
    )
    (comp (ref "R49")
      (value "10KΩ/1%")
      (footprint "0603_R")
      (description "电阻")
      (libsource (lib "Integrated_Library") (part "RES2"))
    )
    (comp (ref "R50")
      (value "10KΩ/1%")
      (footprint "0603_R")
      (description "电阻")
      (libsource (lib "Integrated_Library") (part "RES2"))
    )
    (comp (ref "R51")
      (value "10KΩ/1%")
      (footprint "0603_R")
      (description "电阻")
      (libsource (lib "Integrated_Library") (part "RES2"))
    )
    (comp (ref "R52")
      (value "0Ω")
      (footprint "1812_R")
      (description "电阻")
      (libsource (lib "Integrated_Library") (part "RES2"))
    )
    (comp (ref "R53")
      (value "10KΩ/1%")
      (footprint "0603_R")
      (description "电阻")
      (libsource (lib "Integrated_Library") (part "RES2"))
    )
    (comp (ref "R54")
      (value "RES2")
      (footprint "0603_R")
      (description "电阻")
      (libsource (lib "Integrated_Library") (part "RES2"))
    )
    (comp (ref "R55")
      (value "10KΩ/1%")
      (footprint "0603_R")
      (description "电阻")
      (libsource (lib "Integrated_Library") (part "RES2"))
    )
    (comp (ref "R56")
      (value "RES2")
      (footprint "0603_R")
      (description "电阻")
      (libsource (lib "Integrated_Library") (part "RES2"))
    )
    (comp (ref "R57")
      (value "10KΩ/1%")
      (footprint "0603_R")
      (description "电阻")
      (libsource (lib "Integrated_Library") (part "RES2"))
    )
    (comp (ref "R58")
      (value "10KΩ/1%")
      (footprint "0603_R")
      (description "电阻")
      (libsource (lib "Integrated_Library") (part "RES2"))
    )
    (comp (ref "R59")
      (value "10KΩ/1%")
      (footprint "0603_R")
      (description "电阻")
      (libsource (lib "Integrated_Library") (part "RES2"))
    )
    (comp (ref "R60")
      (value "10KΩ/1%")
      (footprint "0603_R")
      (description "电阻")
      (libsource (lib "Integrated_Library") (part "RES2"))
    )
    (comp (ref "R61")
      (value "10KΩ/1%")
      (footprint "0603_R")
      (description "电阻")
      (libsource (lib "Integrated_Library") (part "RES2"))
    )
    (comp (ref "R62")
      (value "470Ω/1%")
      (footprint "0603_R")
      (description "电阻")
      (libsource (lib "Integrated_Library") (part "RES2"))
    )
    (comp (ref "R63")
      (value "470Ω/1%")
      (footprint "0603_R")
      (description "电阻")
      (libsource (lib "Integrated_Library") (part "RES2"))
    )
    (comp (ref "R64")
      (value "10KΩ/1%")
      (footprint "0603_R")
      (description "电阻")
      (libsource (lib "Integrated_Library") (part "RES2"))
    )
    (comp (ref "R65")
      (value "10KΩ/1%")
      (footprint "0603_R")
      (description "电阻")
      (libsource (lib "Integrated_Library") (part "RES2"))
    )
    (comp (ref "R66")
      (value "10KΩ/1%")
      (footprint "0603_R")
      (description "电阻")
      (libsource (lib "Integrated_Library") (part "RES2"))
    )
    (comp (ref "R67")
      (value "470Ω/1%")
      (footprint "0603_R")
      (description "电阻")
      (libsource (lib "Integrated_Library") (part "RES2"))
    )
    (comp (ref "R68")
      (value "10KΩ/1%")
      (footprint "0603_R")
      (description "电阻")
      (libsource (lib "Integrated_Library") (part "RES2"))
    )
    (comp (ref "R69")
      (value "10KΩ/1%")
      (footprint "0603_R")
      (description "电阻")
      (libsource (lib "Integrated_Library") (part "RES2"))
    )
    (comp (ref "R70")
      (value "100KΩ/1%")
      (footprint "0603_R")
      (description "电阻")
      (libsource (lib "Integrated_Library") (part "RES2"))
    )
    (comp (ref "R71")
      (value "100MΩ")
      (footprint "0603_R")
      (description "电阻")
      (libsource (lib "Integrated_Library") (part "RES2"))
    )
    (comp (ref "R72")
      (value "10KΩ/1%")
      (footprint "0603_R")
      (description "电阻")
      (libsource (lib "Integrated_Library") (part "RES2"))
    )
    (comp (ref "R73")
      (value "10KΩ/1%")
      (footprint "0603_R")
      (description "电阻")
      (libsource (lib "Integrated_Library") (part "RES2"))
    )
    (comp (ref "R74")
      (value "10KΩ/1%")
      (footprint "0603_R")
      (description "电阻")
      (libsource (lib "Integrated_Library") (part "RES2"))
    )
    (comp (ref "R75")
      (value "100MΩ")
      (footprint "0603_R")
      (description "电阻")
      (libsource (lib "Integrated_Library") (part "RES2"))
    )
    (comp (ref "R76")
      (value "10KΩ/1%")
      (footprint "0603_R")
      (description "电阻")
      (libsource (lib "Integrated_Library") (part "RES2"))
    )
    (comp (ref "R77")
      (value "100KΩ/1%")
      (footprint "0603_R")
      (description "电阻")
      (libsource (lib "Integrated_Library") (part "RES2"))
    )
    (comp (ref "R78")
      (value "10KΩ/1%")
      (footprint "0603_R")
      (description "电阻")
      (libsource (lib "Integrated_Library") (part "RES2"))
    )
    (comp (ref "R79")
      (value "10KΩ/1%")
      (footprint "0603_R")
      (description "电阻")
      (libsource (lib "Integrated_Library") (part "RES2"))
    )
    (comp (ref "R80")
      (value "10KΩ/1%")
      (footprint "0603_R")
      (description "电阻")
      (libsource (lib "Integrated_Library") (part "RES2"))
    )
    (comp (ref "R81")
      (value "10KΩ/1%")
      (footprint "0603_R")
      (description "电阻")
      (libsource (lib "Integrated_Library") (part "RES2"))
    )
    (comp (ref "R82")
      (value "10KΩ/1%")
      (footprint "0603_R")
      (description "电阻")
      (libsource (lib "Integrated_Library") (part "RES2"))
    )
    (comp (ref "R83")
      (value "10KΩ/1%")
      (footprint "0603_R")
      (description "电阻")
      (libsource (lib "Integrated_Library") (part "RES2"))
    )
    (comp (ref "R84")
      (value "1MΩ")
      (footprint "0603_R")
      (description "电阻")
      (libsource (lib "Integrated_Library") (part "RES2"))
    )
    (comp (ref "R85")
      (value "0.82Ω/1%")
      (footprint "1812_R")
      (description "电阻")
      (libsource (lib "Integrated_Library") (part "RES2"))
    )
    (comp (ref "R86")
      (value "10KΩ/1%")
      (footprint "0603_R")
      (description "电阻")
      (libsource (lib "Integrated_Library") (part "RES2"))
    )
    (comp (ref "R87")
      (value "1KΩ x 4")
      (footprint "0402_Rx4")
      (description "排阻")
      (libsource (lib "Integrated_Library") (part "Res Pack x4"))
    )
    (comp (ref "R88")
      (value "1KΩ x 4")
      (footprint "0402_Rx4")
      (description "排阻")
      (libsource (lib "Integrated_Library") (part "Res Pack x4"))
    )
    (comp (ref "R89")
      (value "10KΩ/1%")
      (footprint "0603_R")
      (description "电阻")
      (libsource (lib "Integrated_Library") (part "RES2"))
    )
    (comp (ref "R90")
      (value "10KΩ/1%")
      (footprint "0603_R")
      (description "电阻")
      (libsource (lib "Integrated_Library") (part "RES2"))
    )
    (comp (ref "R91")
      (value "10KΩ/1%")
      (footprint "0603_R")
      (description "电阻")
      (libsource (lib "Integrated_Library") (part "RES2"))
    )
    (comp (ref "R92")
      (value "1KΩ x 4")
      (footprint "0402_Rx4")
      (description "排阻")
      (libsource (lib "Integrated_Library") (part "Res Pack x4"))
    )
    (comp (ref "R93")
      (value "10KΩ/1%")
      (footprint "0603_R")
      (description "电阻")
      (libsource (lib "Integrated_Library") (part "RES2"))
    )
    (comp (ref "R94")
      (value "10KΩ/1%")
      (footprint "0603_R")
      (description "电阻")
      (libsource (lib "红牛板Schlib") (part "RES2"))
    )
    (comp (ref "R95")
      (value "470Ω/1%")
      (footprint "0603_R")
      (description "电阻")
      (libsource (lib "Integrated_Library") (part "RES2"))
    )
    (comp (ref "R96")
      (value "10KΩ/1%")
      (footprint "0603_R")
      (description "电阻")
      (libsource (lib "红牛板Schlib") (part "RES2"))
    )
    (comp (ref "R97")
      (value "1KΩ x 4")
      (footprint "0402_Rx4")
      (description "排阻")
      (libsource (lib "Integrated_Library") (part "Res Pack x4"))
    )
    (comp (ref "R98")
      (value "4.7KΩ/1%")
      (footprint "0603_R")
      (description "电阻")
      (libsource (lib "Integrated_Library") (part "RES2"))
    )
    (comp (ref "R99")
      (value "10KΩ[电位器]")
      (footprint "3362P")
      (description "可调电位器")
      (libsource (lib "Integrated_Library") (part "POT2"))
    )
    (comp (ref "R100")
      (value "4.7KΩ/1%")
      (footprint "0603_R")
      (description "电阻")
      (libsource (lib "Integrated_Library") (part "RES2"))
    )
    (comp (ref "R101")
      (value "10KΩ/1%")
      (footprint "0603_R")
      (description "电阻")
      (libsource (lib "红牛板Schlib") (part "RES2"))
    )
    (comp (ref "R102")
      (value "10KΩ/1%")
      (footprint "0603_R")
      (description "电阻")
      (libsource (lib "Integrated_Library") (part "RES2"))
    )
    (comp (ref "R103")
      (value "470Ω/1%")
      (footprint "0603_R")
      (description "电阻")
      (libsource (lib "Integrated_Library") (part "RES2"))
    )
    (comp (ref "R104")
      (value "4.7KΩ/1%")
      (footprint "0603_R")
      (description "电阻")
      (libsource (lib "Integrated_Library") (part "RES2"))
    )
    (comp (ref "R105")
      (value "4.7KΩ/1%")
      (footprint "0603_R")
      (description "电阻")
      (libsource (lib "Integrated_Library") (part "RES2"))
    )
    (comp (ref "R106")
      (value "4.7KΩ/1%")
      (footprint "0603_R")
      (description "电阻")
      (libsource (lib "Integrated_Library") (part "RES2"))
    )
    (comp (ref "R107")
      (value "4.7KΩ/1%")
      (footprint "0603_R")
      (description "电阻")
      (libsource (lib "Integrated_Library") (part "RES2"))
    )
    (comp (ref "R108")
      (value "4.7KΩ/1%")
      (footprint "0603_R")
      (description "电阻")
      (libsource (lib "Integrated_Library") (part "RES2"))
    )
    (comp (ref "R109")
      (value "4.7KΩ/1%")
      (footprint "0603_R")
      (description "电阻")
      (libsource (lib "Integrated_Library") (part "RES2"))
    )
    (comp (ref "R110")
      (value "4.7KΩ/1%")
      (footprint "0603_R")
      (description "电阻")
      (libsource (lib "Integrated_Library") (part "RES2"))
    )
    (comp (ref "R111")
      (value "4.7KΩ/1%")
      (footprint "0603_R")
      (description "电阻")
      (libsource (lib "Integrated_Library") (part "RES2"))
    )
    (comp (ref "R112")
      (value "4.7KΩ/1%")
      (footprint "0603_R")
      (description "电阻")
      (libsource (lib "Integrated_Library") (part "RES2"))
    )
    (comp (ref "R113")
      (value "4.7KΩ/1%")
      (footprint "0603_R")
      (description "电阻")
      (libsource (lib "Integrated_Library") (part "RES2"))
    )
    (comp (ref "R114")
      (value "4.7KΩ/1%")
      (footprint "0603_R")
      (description "电阻")
      (libsource (lib "Integrated_Library") (part "RES2"))
    )
    (comp (ref "R115")
      (value "4.7KΩ/1%")
      (footprint "0603_R")
      (description "电阻")
      (libsource (lib "Integrated_Library") (part "RES2"))
    )
    (comp (ref "R116")
      (value "4.7KΩ/1%")
      (footprint "0603_R")
      (description "电阻")
      (libsource (lib "Integrated_Library") (part "RES2"))
    )
    (comp (ref "R117")
      (value "4.7KΩ/1%")
      (footprint "0603_R")
      (description "电阻")
      (libsource (lib "Integrated_Library") (part "RES2"))
    )
    (comp (ref "R118")
      (value "4.7KΩ/1%")
      (footprint "0603_R")
      (description "电阻")
      (libsource (lib "Integrated_Library") (part "RES2"))
    )
    (comp (ref "R119")
      (value "4.7KΩ/1%")
      (footprint "0603_R")
      (description "电阻")
      (libsource (lib "Integrated_Library") (part "RES2"))
    )
    (comp (ref "S1")
      (value "SW-PB")
      (footprint "SW-TH_4P-L12.0-W12.0-P5.00-LS12.5")
      (description "轻触开关")
      (libsource (lib "MyLib Schlib") (part "SW-PB"))
    )
    (comp (ref "S2")
      (value "SW-PB")
      (footprint "SW-6*6")
      (description "轻触开关")
      (libsource (lib "Integrated_Library") (part "SW-PB"))
    )
    (comp (ref "S3")
      (value "SW-PB")
      (footprint "SW-6*6")
      (description "轻触开关")
      (libsource (lib "MyLib Schlib") (part "SW-PB"))
    )
    (comp (ref "S4")
      (value "SW-PB")
      (footprint "SW-6*6")
      (description "轻触开关")
      (libsource (lib "MyLib Schlib") (part "SW-PB"))
    )
    (comp (ref "U4")
      (value "M482KIDAE")
      (footprint "LQFP-128_L14.0-W14.0-P0.40-LS16.0-BL")
      (description "新唐 M482KIDAE")
      (libsource (lib "MyLib Schlib") (part "M482KIDAE"))
    )
    (comp (ref "U5")
      (value "NCE603S")
      (footprint "SO-8（1.27/3.8*5）")
      (description "互补型mos")
      (libsource (lib "Integrated_Library") (part "AO4611"))
    )
    (comp (ref "U6")
      (value "ST3485ECDR")
      (footprint "SO-8（1.27/3.8*5）")
      (description "485总线收发器（3.3V）")
      (libsource (lib "Integrated_Library") (part "MAX3485"))
    )
    (comp (ref "U7")
      (value "NCE603S")
      (footprint "SO-8（1.27/3.8*5）")
      (description "互补型mos")
      (libsource (lib "Integrated_Library") (part "AO4611"))
    )
    (comp (ref "U8")
      (value "AMS1084-ADJ")
      (footprint "TO-252")
      (description "LDO电压转换")
      (libsource (lib "Integrated_Library") (part "AMS1084-ADJ"))
    )
    (comp (ref "U9")
      (value "NCE603S")
      (footprint "SO-8（1.27/3.8*5）")
      (description "互补型mos")
      (libsource (lib "Integrated_Library") (part "AO4611"))
    )
    (comp (ref "U10")
      (value "FM24CL64B")
      (footprint "SO-8（1.27/3.8*5）")
      (description "CYPRESS-64Kbit")
      (libsource (lib "Integrated_Library") (part "FM24CL64B"))
    )
    (comp (ref "U11")
      (value "NCE603S")
      (footprint "SO-8（1.27/3.8*5）")
      (description "互补型mos")
      (libsource (lib "Integrated_Library") (part "AO4611"))
    )
    (comp (ref "U12")
      (value "TPS54531")
      (footprint "SO-8-POWERPAD（1.27/3.8*5）")
      (description "DC-DC/5A")
      (libsource (lib "MyLib Schlib") (part "TPS54531"))
    )
    (comp (ref "U13")
      (value "GC1307")
      (footprint "SO-8（1.27/3.8*5）")
      (description "RTC 芯片")
      (libsource (lib "Integrated_Library") (part "GC1307"))
    )
    (comp (ref "U14")
      (value "NCE603S")
      (footprint "SO-8（1.27/3.8*5）")
      (description "互补型mos")
      (libsource (lib "Integrated_Library") (part "AO4611"))
    )
    (comp (ref "U15")
      (value "74HC595")
      (footprint "SO-16（1.27/3.8*10）")
      (description "串入并出移位寄存器")
      (libsource (lib "Integrated_Library") (part "74HC595"))
    )
    (comp (ref "U16")
      (value "NCE603S")
      (footprint "SO-8（1.27/3.8*5）")
      (description "互补型mos")
      (libsource (lib "Integrated_Library") (part "AO4611"))
    )
    (comp (ref "U17")
      (value "NCE603S")
      (footprint "SO-8（1.27/3.8*5）")
      (description "互补型mos")
      (libsource (lib "Integrated_Library") (part "AO4611"))
    )
    (comp (ref "U18")
      (value "NCE603S")
      (footprint "SO-8（1.27/3.8*5）")
      (description "互补型mos")
      (libsource (lib "Integrated_Library") (part "AO4611"))
    )
    (comp (ref "U19")
      (value "NCE603S")
      (footprint "SO-8（1.27/3.8*5）")
      (description "互补型mos")
      (libsource (lib "Integrated_Library") (part "AO4611"))
    )
    (comp (ref "U20")
      (value "NCE603S")
      (footprint "SO-8（1.27/3.8*5）")
      (description "互补型mos")
      (libsource (lib "Integrated_Library") (part "AO4611"))
    )
    (comp (ref "U21")
      (value "NCV2904")
      (footprint "SO-8（1.27/3.8*5）")
      (description "双运放")
      (libsource (lib "Integrated_Library") (part "DUAL OPAMP"))
    )
    (comp (ref "U22")
      (value "BUZZER 9055/3V")
      (footprint "BUZZ-9055/5.0mm")
      (description "有源蜂鸣器-9055/3V")
      (libsource (lib "Integrated_Library") (part "BUZZER"))
    )
    (comp (ref "U23")
      (value "ST3232CDR")
      (footprint "SO-16（1.27/3.8*10）")
      (description "RS232电平转换/3.3V")
      (libsource (lib "Integrated_Library") (part "ST3232"))
    )
    (comp (ref "X1")
      (value "32.768KHZ / 6PF / ±10PPM")
      (footprint "SMD-3215-2P")
      (description "无源晶振")
      (libsource (lib "红牛板Schlib") (part "CRYSTAL"))
    )
    (comp (ref "X2")
      (value "12MHZ / 20PF / ±10PPM")
      (footprint "SMD-5032_2P")
      (description "无源晶振2脚")
      (libsource (lib "Integrated_Library") (part "CRYSTAL_2P"))
    )
  )
  (nets
    (net (code "1") (name "/4G_POWER") (class "Default")
      (node (ref "J3") (pin "1") (pinfunction "1_1") (pintype "passive"))
      (node (ref "U4") (pin "57") (pinfunction "PA3_57") (pintype "passive"))
    )
    (net (code "2") (name "/4G_RX") (class "Default")
      (node (ref "J3") (pin "3") (pinfunction "3_3") (pintype "passive"))
      (node (ref "U4") (pin "56") (pinfunction "PA4/UART5_RXD_56") (pintype "passive"))
    )
    (net (code "3") (name "/4G_TX") (class "Default")
      (node (ref "J3") (pin "2") (pinfunction "2_2") (pintype "passive"))
      (node (ref "U4") (pin "55") (pinfunction "PA5/UART5_TXD_55") (pintype "passive"))
    )
    (net (code "4") (name "/485_A") (class "Default")
      (node (ref "J4") (pin "1") (pinfunction "1_1") (pintype "passive"))
      (node (ref "R20") (pin "1") (pinfunction "1_1") (pintype "passive"))
      (node (ref "R24") (pin "2") (pinfunction "2_2") (pintype "passive"))
      (node (ref "U6") (pin "6") (pinfunction "A_6") (pintype "passive"))
    )
    (net (code "5") (name "/485_B") (class "Default")
      (node (ref "J4") (pin "2") (pinfunction "2_2") (pintype "passive"))
      (node (ref "R16") (pin "1") (pinfunction "1_1") (pintype "passive"))
      (node (ref "R20") (pin "2") (pinfunction "2_2") (pintype "passive"))
      (node (ref "U6") (pin "7") (pinfunction "B_7") (pintype "passive"))
    )
    (net (code "6") (name "/485_RX") (class "Default")
      (node (ref "U4") (pin "49") (pinfunction "PC6/UART4_RXD_49") (pintype "passive"))
      (node (ref "U6") (pin "1") (pinfunction "RO_1") (pintype "passive"))
    )
    (net (code "7") (name "/485_TX") (class "Default")
      (node (ref "R22") (pin "1") (pinfunction "1_1") (pintype "passive"))
      (node (ref "U4") (pin "48") (pinfunction "PC7/UART4_TXD_48") (pintype "passive"))
      (node (ref "U6") (pin "4") (pinfunction "DI_4") (pintype "passive"))
    )
    (net (code "8") (name "/AVDD") (class "Default")
      (node (ref "C37") (pin "1") (pinfunction "1_1") (pintype "passive"))
      (node (ref "C38") (pin "1") (pinfunction "1_1") (pintype "passive"))
      (node (ref "C39") (pin "1") (pinfunction "1_1") (pintype "passive"))
      (node (ref "L3") (pin "2") (pinfunction "2_2") (pintype "passive"))
      (node (ref "U4") (pin "120") (pinfunction "AVDD_120") (pintype "passive"))
    )
    (net (code "9") (name "/AVSS") (class "Default")
      (node (ref "C34") (pin "2") (pinfunction "2_2") (pintype "passive"))
      (node (ref "C35") (pin "2") (pinfunction "2_2") (pintype "passive"))
      (node (ref "C36") (pin "2") (pinfunction "2_2") (pintype "passive"))
      (node (ref "C37") (pin "2") (pinfunction "2_2") (pintype "passive"))
      (node (ref "C38") (pin "2") (pinfunction "2_2") (pintype "passive"))
      (node (ref "C39") (pin "2") (pinfunction "2_2") (pintype "passive"))
      (node (ref "L4") (pin "2") (pinfunction "2_2") (pintype "passive"))
      (node (ref "U4") (pin "122") (pinfunction "AVSS_122") (pintype "passive"))
    )
    (net (code "10") (name "/BAT_TEST") (class "Default")
      (node (ref "R71") (pin "1") (pinfunction "1_1") (pintype "passive"))
      (node (ref "R75") (pin "2") (pinfunction "2_2") (pintype "passive"))
      (node (ref "U4") (pin "3") (pinfunction "PB3/EADC0_CH3_3") (pintype "passive"))
    )
    (net (code "11") (name "/BEEP") (class "Default")
      (node (ref "R98") (pin "1") (pinfunction "1_1") (pintype "passive"))
      (node (ref "U4") (pin "71") (pinfunction "PC3_71") (pintype "passive"))
    )
    (net (code "12") (name "/BKP1_RX") (class "Default")
      (node (ref "U4") (pin "15") (pinfunction "PA9/SC2_DAT/RX_15") (pintype "passive"))
    )
    (net (code "13") (name "/BKP1_TX") (class "Default")
      (node (ref "U4") (pin "16") (pinfunction "PA8/SC2_CLK/TX_16") (pintype "passive"))
    )
    (net (code "14") (name "/BKP2_RX") (class "Default")
      (node (ref "U4") (pin "28") (pinfunction "PF7/SC0_DAT/RX_28") (pintype "passive"))
    )
    (net (code "15") (name "/BKP2_TX") (class "Default")
      (node (ref "U4") (pin "29") (pinfunction "PF6/SC0_CLK/TX_29") (pintype "passive"))
    )
    (net (code "16") (name "/BKP3_RX") (class "Default")
      (node (ref "U4") (pin "73") (pinfunction "PC1/SC1_DAT/RX_73") (pintype "passive"))
    )
    (net (code "17") (name "/BKP3_TX") (class "Default")
      (node (ref "U4") (pin "74") (pinfunction "PC0/SC1_CLK/TX_74") (pintype "passive"))
    )
    (net (code "18") (name "/CARD_RX") (class "Default")
      (node (ref "U23") (pin "9") (pinfunction "R2out_9") (pintype "passive"))
      (node (ref "U4") (pin "8") (pinfunction "PC9/UART3_RXD_8") (pintype "passive"))
    )
    (net (code "19") (name "/CARD_TX") (class "Default")
      (node (ref "U23") (pin "10") (pinfunction "T2in_10") (pintype "passive"))
      (node (ref "U4") (pin "7") (pinfunction "PC10/UART3_TXD_7") (pintype "passive"))
    )
    (net (code "21") (name "/DOOR") (class "Default")
      (node (ref "J7") (pin "2") (pinfunction "2_2") (pintype "passive"))
      (node (ref "R90") (pin "1") (pinfunction "1_1") (pintype "passive"))
      (node (ref "U4") (pin "72") (pinfunction "PC2_72") (pintype "passive"))
    )
    (net (code "22") (name "/DROP_CT") (class "Default")
      (node (ref "R102") (pin "1") (pinfunction "1_1") (pintype "passive"))
      (node (ref "U4") (pin "69") (pinfunction "PC5_69") (pintype "passive"))
    )
    (net (code "23") (name "/DROP_CT_OUT") (class "Default")
      (node (ref "D38") (pin "2") (pinfunction "K_2") (pintype "passive"))
    )
    (net (code "24") (name "/DROP_SIG") (class "Default")
      (node (ref "C59") (pin "1") (pinfunction "1_1") (pintype "passive"))
      (node (ref "D39") (pin "1") (pinfunction "A_1") (pintype "passive"))
      (node (ref "R100") (pin "1") (pinfunction "1_1") (pintype "passive"))
      (node (ref "U4") (pin "70") (pinfunction "PC4_70") (pintype "passive"))
    )
    (net (code "25") (name "/DROP_SIG_OUT") (class "Default")
      (node (ref "R103") (pin "2") (pinfunction "2_2") (pintype "passive"))
    )
    (net (code "26") (name "/EXT1") (class "Default")
      (node (ref "U15") (pin "15") (pinfunction "Q0_15") (pintype "passive"))
    )
    (net (code "27") (name "/EXT2") (class "Default")
      (node (ref "U15") (pin "1") (pinfunction "Q1_1") (pintype "passive"))
    )
    (net (code "28") (name "/EXT3") (class "Default")
      (node (ref "U15") (pin "2") (pinfunction "Q2_2") (pintype "passive"))
    )
    (net (code "29") (name "/EXT4") (class "Default")
      (node (ref "U15") (pin "3") (pinfunction "Q3_3") (pintype "passive"))
    )
    (net (code "30") (name "/EXT5") (class "Default")
      (node (ref "U15") (pin "4") (pinfunction "Q4_4") (pintype "passive"))
    )
    (net (code "31") (name "/EXT6") (class "Default")
      (node (ref "U15") (pin "5") (pinfunction "Q5_5") (pintype "passive"))
    )
    (net (code "32") (name "/EXT7") (class "Default")
      (node (ref "U15") (pin "6") (pinfunction "Q6_6") (pintype "passive"))
    )
    (net (code "33") (name "/EXT8") (class "Default")
      (node (ref "U15") (pin "7") (pinfunction "Q7_7") (pintype "passive"))
    )
    (net (code "34") (name "/FACE_RX") (class "Default")
      (node (ref "U4") (pin "42") (pinfunction "PE9/UART2_RXD_42") (pintype "passive"))
    )
    (net (code "35") (name "/FACE_TX") (class "Default")
      (node (ref "U4") (pin "41") (pinfunction "PE8/UART2_TXD_41") (pintype "passive"))
    )
    (net (code "38") (name "/I2C0_SCL") (class "Default")
      (node (ref "R35") (pin "1") (pinfunction "1_1") (pintype "passive"))
      (node (ref "U10") (pin "6") (pinfunction "SCL_6") (pintype "passive"))
      (node (ref "U4") (pin "46") (pinfunction "PE13/I2C0_SCL_46") (pintype "passive"))
    )
    (net (code "39") (name "/I2C0_SDA") (class "Default")
      (node (ref "R36") (pin "1") (pinfunction "1_1") (pintype "passive"))
      (node (ref "U10") (pin "5") (pinfunction "SDA_5") (pintype "passive"))
      (node (ref "U4") (pin "47") (pinfunction "PC8/I2C0_SDA_47") (pintype "passive"))
    )
    (net (code "40") (name "/I2C1_SCL") (class "Default")
      (node (ref "R45") (pin "1") (pinfunction "1_1") (pintype "passive"))
      (node (ref "U13") (pin "6") (pinfunction "SCL_6") (pintype "passive"))
      (node (ref "U4") (pin "21") (pinfunction "PG2/I2C1_SCL_21") (pintype "passive"))
    )
    (net (code "41") (name "/I2C1_SDA") (class "Default")
      (node (ref "R46") (pin "1") (pinfunction "1_1") (pintype "passive"))
      (node (ref "U13") (pin "5") (pinfunction "SDA_5") (pintype "passive"))
      (node (ref "U4") (pin "22") (pinfunction "PG3/I2C1_SDA_22") (pintype "passive"))
    )
    (net (code "42") (name "/ICE_CLK") (class "Default")
      (node (ref "D29") (pin "1") (pinfunction "1_1") (pintype "passive"))
      (node (ref "J6") (pin "3") (pinfunction "3_3") (pintype "passive"))
      (node (ref "R70") (pin "1") (pinfunction "1_1") (pintype "passive"))
      (node (ref "U4") (pin "66") (pinfunction "PF1/ICE_CLK_66") (pintype "passive"))
    )
    (net (code "43") (name "/ICE_DAT") (class "Default")
      (node (ref "D30") (pin "1") (pinfunction "1_1") (pintype "passive"))
      (node (ref "J6") (pin "2") (pinfunction "2_2") (pintype "passive"))
      (node (ref "R77") (pin "2") (pinfunction "2_2") (pintype "passive"))
      (node (ref "U4") (pin "65") (pinfunction "PF0/ICE_DAT_65") (pintype "passive"))
    )
    (net (code "44") (name "/INFO_BUTTON") (class "Default")
      (node (ref "R96") (pin "2") (pinfunction "2_2") (pintype "passive"))
      (node (ref "S3") (pin "1") (pinfunction "1_1") (pintype "passive"))
      (node (ref "U4") (pin "60") (pinfunction "PA0_60") (pintype "passive"))
    )
    (net (code "45") (name "/KEY1") (class "Default")
      (node (ref "Q31") (pin "3") (pinfunction "3_3") (pintype "passive"))
      (node (ref "R112") (pin "1") (pinfunction "1_1") (pintype "passive"))
      (node (ref "U4") (pin "36") (pinfunction "PH7_36") (pintype "passive"))
    )
    (net (code "46") (name "/KEY1_IN") (class "Default")
      (node (ref "D47") (pin "1") (pinfunction "1_1") (pintype "passive"))
      (node (ref "R116") (pin "1") (pinfunction "1_1") (pintype "passive"))
    )
    (net (code "47") (name "/KEY2") (class "Default")
      (node (ref "Q32") (pin "3") (pinfunction "3_3") (pintype "passive"))
      (node (ref "R113") (pin "1") (pinfunction "1_1") (pintype "passive"))
      (node (ref "U4") (pin "35") (pinfunction "PH6_35") (pintype "passive"))
    )
    (net (code "48") (name "/KEY2_IN") (class "Default")
      (node (ref "D46") (pin "1") (pinfunction "1_1") (pintype "passive"))
      (node (ref "R117") (pin "1") (pinfunction "1_1") (pintype "passive"))
    )
    (net (code "49") (name "/KEY3") (class "Default")
      (node (ref "Q33") (pin "3") (pinfunction "3_3") (pintype "passive"))
      (node (ref "R114") (pin "1") (pinfunction "1_1") (pintype "passive"))
      (node (ref "U4") (pin "34") (pinfunction "PH5_34") (pintype "passive"))
    )
    (net (code "50") (name "/KEY3_IN") (class "Default")
      (node (ref "D45") (pin "1") (pinfunction "1_1") (pintype "passive"))
      (node (ref "R118") (pin "1") (pinfunction "1_1") (pintype "passive"))
    )
    (net (code "51") (name "/KEY4") (class "Default")
      (node (ref "Q34") (pin "3") (pinfunction "3_3") (pintype "passive"))
      (node (ref "R115") (pin "1") (pinfunction "1_1") (pintype "passive"))
      (node (ref "U4") (pin "33") (pinfunction "PH4_33") (pintype "passive"))
    )
    (net (code "52") (name "/KEY4_IN") (class "Default")
      (node (ref "D44") (pin "1") (pinfunction "1_1") (pintype "passive"))
      (node (ref "R119") (pin "1") (pinfunction "1_1") (pintype "passive"))
    )
    (net (code "53") (name "/KEY5") (class "Default")
      (node (ref "R104") (pin "1") (pinfunction "1_1") (pintype "passive"))
      (node (ref "U4") (pin "27") (pinfunction "PF8_27") (pintype "passive"))
    )
    (net (code "54") (name "/KEY5_IN") (class "Default")
      (node (ref "D43") (pin "1") (pinfunction "1_1") (pintype "passive"))
      (node (ref "Q27") (pin "3") (pinfunction "3_3") (pintype "passive"))
      (node (ref "R108") (pin "2") (pinfunction "2_2") (pintype "passive"))
    )
    (net (code "55") (name "/KEY6") (class "Default")
      (node (ref "R105") (pin "1") (pinfunction "1_1") (pintype "passive"))
      (node (ref "U4") (pin "26") (pinfunction "PF9_26") (pintype "passive"))
    )
    (net (code "56") (name "/KEY6_IN") (class "Default")
      (node (ref "D42") (pin "1") (pinfunction "1_1") (pintype "passive"))
      (node (ref "Q28") (pin "3") (pinfunction "3_3") (pintype "passive"))
      (node (ref "R109") (pin "2") (pinfunction "2_2") (pintype "passive"))
    )
    (net (code "57") (name "/KEY7") (class "Default")
      (node (ref "R106") (pin "1") (pinfunction "1_1") (pintype "passive"))
      (node (ref "U4") (pin "25") (pinfunction "PF10_25") (pintype "passive"))
    )
    (net (code "58") (name "/KEY7_IN") (class "Default")
      (node (ref "D41") (pin "1") (pinfunction "1_1") (pintype "passive"))
      (node (ref "Q29") (pin "3") (pinfunction "3_3") (pintype "passive"))
      (node (ref "R110") (pin "2") (pinfunction "2_2") (pintype "passive"))
    )
    (net (code "59") (name "/KEY8") (class "Default")
      (node (ref "R107") (pin "1") (pinfunction "1_1") (pintype "passive"))
      (node (ref "U4") (pin "24") (pinfunction "PF11_24") (pintype "passive"))
    )
    (net (code "60") (name "/KEY8_IN") (class "Default")
      (node (ref "D40") (pin "1") (pinfunction "1_1") (pintype "passive"))
      (node (ref "Q30") (pin "3") (pinfunction "3_3") (pintype "passive"))
      (node (ref "R111") (pin "2") (pinfunction "2_2") (pintype "passive"))
    )
    (net (code "61") (name "/LCD_CS") (class "Default")
      (node (ref "R97") (pin "5") (pinfunction "5_5") (pintype "passive"))
      (node (ref "U4") (pin "18") (pinfunction "PD12/EBI_nCS0_18") (pintype "passive"))
    )
    (net (code "62") (name "/LCD_D0") (class "Default")
      (node (ref "R87") (pin "7") (pinfunction "7_7") (pintype "passive"))
      (node (ref "U4") (pin "77") (pinfunction "PG9/EBI_AD0_77") (pintype "passive"))
    )
    (net (code "63") (name "/LCD_D1") (class "Default")
      (node (ref "R88") (pin "8") (pinfunction "8_8") (pintype "passive"))
      (node (ref "U4") (pin "78") (pinfunction "PG10/EBI_AD1_78") (pintype "passive"))
    )
    (net (code "64") (name "/LCD_D2") (class "Default")
      (node (ref "R88") (pin "7") (pinfunction "7_7") (pintype "passive"))
      (node (ref "U4") (pin "79") (pinfunction "PG11/EBI_AD2_79") (pintype "passive"))
    )
    (net (code "65") (name "/LCD_D3") (class "Default")
      (node (ref "R88") (pin "6") (pinfunction "6_6") (pintype "passive"))
      (node (ref "U4") (pin "80") (pinfunction "PG12/EBI_AD3_80") (pintype "passive"))
    )
    (net (code "66") (name "/LCD_D4") (class "Default")
      (node (ref "R88") (pin "5") (pinfunction "5_5") (pintype "passive"))
      (node (ref "U4") (pin "81") (pinfunction "PG13/EBI_AD4_81") (pintype "passive"))
    )
    (net (code "67") (name "/LCD_D5") (class "Default")
      (node (ref "R92") (pin "8") (pinfunction "8_8") (pintype "passive"))
      (node (ref "U4") (pin "82") (pinfunction "PG14/EBI_AD5_82") (pintype "passive"))
    )
    (net (code "68") (name "/LCD_D6") (class "Default")
      (node (ref "R92") (pin "7") (pinfunction "7_7") (pintype "passive"))
      (node (ref "U4") (pin "68") (pinfunction "PD8/EBI_AD6_68") (pintype "passive"))
    )
    (net (code "69") (name "/LCD_D7") (class "Default")
      (node (ref "R92") (pin "6") (pinfunction "6_6") (pintype "passive"))
      (node (ref "U4") (pin "67") (pinfunction "PD9/EBI_AD7_67") (pintype "passive"))
    )
    (net (code "70") (name "/LCD_RD") (class "Default")
      (node (ref "R97") (pin "8") (pinfunction "8_8") (pintype "passive"))
      (node (ref "U4") (pin "13") (pinfunction "PA11/EBI_nRD_13") (pintype "passive"))
    )
    (net (code "71") (name "/LCD_RS") (class "Default")
      (node (ref "R92") (pin "5") (pinfunction "5_5") (pintype "passive"))
      (node (ref "U4") (pin "17") (pinfunction "PC13/EBI_ADR10_17") (pintype "passive"))
    )
    (net (code "72") (name "/LCD_RST") (class "Default")
      (node (ref "R87") (pin "8") (pinfunction "8_8") (pintype "passive"))
      (node (ref "U4") (pin "83") (pinfunction "PG15_83") (pintype "passive"))
    )
    (net (code "73") (name "/LCD_WR") (class "Default")
      (node (ref "R97") (pin "7") (pinfunction "7_7") (pintype "passive"))
      (node (ref "U4") (pin "14") (pinfunction "PA10/EBI_nWR_14") (pintype "passive"))
    )
    (net (code "74") (name "/LDO_CAP") (class "Default")
      (node (ref "C44") (pin "1") (pinfunction "1_1") (pintype "passive"))
      (node (ref "C45") (pin "1") (pinfunction "1_1") (pintype "passive"))
      (node (ref "C46") (pin "1") (pinfunction "1_1") (pintype "passive"))
      (node (ref "C47") (pin "1") (pinfunction "1_1") (pintype "passive"))
      (node (ref "C48") (pin "1") (pinfunction "1_1") (pintype "passive"))
      (node (ref "C49") (pin "1") (pinfunction "1_1") (pintype "passive"))
      (node (ref "U4") (pin "113") (pinfunction "LDO_CAP_113") (pintype "passive"))
      (node (ref "U4") (pin "54") (pinfunction "LDO_CAP_54") (pintype "passive"))
      (node (ref "U4") (pin "95") (pinfunction "LDO_CAP_95") (pintype "passive"))
    )
    (net (code "75") (name "/LED_BREATH") (class "Default")
      (node (ref "D23") (pin "2") (pinfunction "2_2") (pintype "passive"))
      (node (ref "U4") (pin "85") (pinfunction "PA12_85") (pintype "passive"))
    )
    (net (code "77") (name "/LED_NET") (class "Default")
      (node (ref "D24") (pin "2") (pinfunction "2_2") (pintype "passive"))
      (node (ref "U4") (pin "84") (pinfunction "PD13_84") (pintype "passive"))
    )
    (net (code "78") (name "/LOG_RX") (class "Default")
      (node (ref "U23") (pin "12") (pinfunction "R1out_12") (pintype "passive"))
      (node (ref "U4") (pin "6") (pinfunction "PC11/UART0_RXD_6") (pintype "passive"))
    )
    (net (code "79") (name "/LOG_TX") (class "Default")
      (node (ref "U23") (pin "11") (pinfunction "T1in_11") (pintype "passive"))
      (node (ref "U4") (pin "5") (pinfunction "PC12/UART0_TXD_5") (pintype "passive"))
    )
    (net (code "80") (name "/L_CS") (class "Default")
      (node (ref "J9") (pin "19") (pinfunction "19_19") (pintype "passive"))
      (node (ref "R97") (pin "4") (pinfunction "4_4") (pintype "passive"))
    )
    (net (code "81") (name "/L_D0") (class "Default")
      (node (ref "J9") (pin "3") (pinfunction "3_3") (pintype "passive"))
      (node (ref "R87") (pin "2") (pinfunction "2_2") (pintype "passive"))
    )
    (net (code "82") (name "/L_D1") (class "Default")
      (node (ref "J9") (pin "13") (pinfunction "13_13") (pintype "passive"))
      (node (ref "R88") (pin "1") (pinfunction "1_1") (pintype "passive"))
    )
    (net (code "83") (name "/L_D2") (class "Default")
      (node (ref "J9") (pin "4") (pinfunction "4_4") (pintype "passive"))
      (node (ref "R88") (pin "2") (pinfunction "2_2") (pintype "passive"))
    )
    (net (code "84") (name "/L_D3") (class "Default")
      (node (ref "J9") (pin "14") (pinfunction "14_14") (pintype "passive"))
      (node (ref "R88") (pin "3") (pinfunction "3_3") (pintype "passive"))
    )
    (net (code "85") (name "/L_D4") (class "Default")
      (node (ref "J9") (pin "5") (pinfunction "5_5") (pintype "passive"))
      (node (ref "R88") (pin "4") (pinfunction "4_4") (pintype "passive"))
    )
    (net (code "86") (name "/L_D5") (class "Default")
      (node (ref "J9") (pin "15") (pinfunction "15_15") (pintype "passive"))
      (node (ref "R92") (pin "1") (pinfunction "1_1") (pintype "passive"))
    )
    (net (code "87") (name "/L_D6") (class "Default")
      (node (ref "J9") (pin "6") (pinfunction "6_6") (pintype "passive"))
      (node (ref "R92") (pin "2") (pinfunction "2_2") (pintype "passive"))
    )
    (net (code "88") (name "/L_D7") (class "Default")
      (node (ref "J9") (pin "16") (pinfunction "16_16") (pintype "passive"))
      (node (ref "R92") (pin "3") (pinfunction "3_3") (pintype "passive"))
    )
    (net (code "89") (name "/L_RD") (class "Default")
      (node (ref "J9") (pin "17") (pinfunction "17_17") (pintype "passive"))
      (node (ref "R97") (pin "1") (pinfunction "1_1") (pintype "passive"))
    )
    (net (code "90") (name "/L_RS") (class "Default")
      (node (ref "J9") (pin "7") (pinfunction "7_7") (pintype "passive"))
      (node (ref "R92") (pin "4") (pinfunction "4_4") (pintype "passive"))
    )
    (net (code "91") (name "/L_RST") (class "Default")
      (node (ref "J9") (pin "2") (pinfunction "2_2") (pintype "passive"))
      (node (ref "R87") (pin "1") (pinfunction "1_1") (pintype "passive"))
    )
    (net (code "92") (name "/L_WR") (class "Default")
      (node (ref "J9") (pin "8") (pinfunction "8_8") (pintype "passive"))
      (node (ref "R97") (pin "2") (pinfunction "2_2") (pintype "passive"))
    )
    (net (code "93") (name "/MDB_RX") (class "Default")
      (node (ref "U4") (pin "20") (pinfunction "PD10/UART1_RXD_20") (pintype "passive"))
    )
    (net (code "94") (name "/MDB_TX") (class "Default")
      (node (ref "U4") (pin "19") (pinfunction "PD11/UART1_TXD_19") (pintype "passive"))
    )
    (net (code "95") (name "/MOTOR_CURRENT") (class "Default")
      (node (ref "R86") (pin "2") (pinfunction "2_2") (pintype "passive"))
      (node (ref "U21") (pin "1") (pinfunction "out1_1") (pintype "passive"))
      (node (ref "U4") (pin "2") (pinfunction "PB4/EADC0_CH4_2") (pintype "passive"))
    )
    (net (code "96") (name "/MOTOR_GND1") (class "Default")
      (node (ref "J5") (pin "20") (pinfunction "20_20") (pintype "passive"))
      (node (ref "U5") (pin "7") (pinfunction "D2_7") (pintype "passive"))
      (node (ref "U5") (pin "8") (pinfunction "D2_8") (pintype "passive"))
    )
    (net (code "97") (name "/MOTOR_GND2") (class "Default")
      (node (ref "J5") (pin "19") (pinfunction "19_19") (pintype "passive"))
      (node (ref "U7") (pin "7") (pinfunction "D2_7") (pintype "passive"))
      (node (ref "U7") (pin "8") (pinfunction "D2_8") (pintype "passive"))
    )
    (net (code "98") (name "/MOTOR_GND3") (class "Default")
      (node (ref "J5") (pin "18") (pinfunction "18_18") (pintype "passive"))
      (node (ref "U9") (pin "7") (pinfunction "D2_7") (pintype "passive"))
      (node (ref "U9") (pin "8") (pinfunction "D2_8") (pintype "passive"))
    )
    (net (code "99") (name "/MOTOR_GND4") (class "Default")
      (node (ref "J5") (pin "17") (pinfunction "17_17") (pintype "passive"))
      (node (ref "U11") (pin "7") (pinfunction "D2_7") (pintype "passive"))
      (node (ref "U11") (pin "8") (pinfunction "D2_8") (pintype "passive"))
    )
    (net (code "100") (name "/MOTOR_GND5") (class "Default")
      (node (ref "J5") (pin "16") (pinfunction "16_16") (pintype "passive"))
      (node (ref "U14") (pin "7") (pinfunction "D2_7") (pintype "passive"))
      (node (ref "U14") (pin "8") (pinfunction "D2_8") (pintype "passive"))
    )
    (net (code "101") (name "/MOTOR_GND6") (class "Default")
      (node (ref "J5") (pin "15") (pinfunction "15_15") (pintype "passive"))
      (node (ref "U16") (pin "7") (pinfunction "D2_7") (pintype "passive"))
      (node (ref "U16") (pin "8") (pinfunction "D2_8") (pintype "passive"))
    )
    (net (code "102") (name "/MOTOR_GND7") (class "Default")
      (node (ref "J5") (pin "14") (pinfunction "14_14") (pintype "passive"))
      (node (ref "U17") (pin "7") (pinfunction "D2_7") (pintype "passive"))
      (node (ref "U17") (pin "8") (pinfunction "D2_8") (pintype "passive"))
    )
    (net (code "103") (name "/MOTOR_GND8") (class "Default")
      (node (ref "J5") (pin "13") (pinfunction "13_13") (pintype "passive"))
      (node (ref "U18") (pin "7") (pinfunction "D2_7") (pintype "passive"))
      (node (ref "U18") (pin "8") (pinfunction "D2_8") (pintype "passive"))
    )
    (net (code "104") (name "/MOTOR_GND9") (class "Default")
      (node (ref "J5") (pin "12") (pinfunction "12_12") (pintype "passive"))
      (node (ref "U19") (pin "7") (pinfunction "D2_7") (pintype "passive"))
      (node (ref "U19") (pin "8") (pinfunction "D2_8") (pintype "passive"))
    )
    (net (code "105") (name "/MOTOR_GND10") (class "Default")
      (node (ref "J5") (pin "11") (pinfunction "11_11") (pintype "passive"))
      (node (ref "U20") (pin "7") (pinfunction "D2_7") (pintype "passive"))
      (node (ref "U20") (pin "8") (pinfunction "D2_8") (pintype "passive"))
    )
    (net (code "106") (name "/MOTOR_L1") (class "Default")
      (node (ref "D7") (pin "1") (pinfunction "A_1") (pintype "passive"))
      (node (ref "U4") (pin "110") (pinfunction "PH11_110") (pintype "passive"))
    )
    (net (code "107") (name "/MOTOR_L2") (class "Default")
      (node (ref "D9") (pin "1") (pinfunction "A_1") (pintype "passive"))
      (node (ref "U4") (pin "108") (pinfunction "PH9_108") (pintype "passive"))
    )
    (net (code "108") (name "/MOTOR_L3") (class "Default")
      (node (ref "D11") (pin "1") (pinfunction "A_1") (pintype "passive"))
      (node (ref "U4") (pin "106") (pinfunction "PE0_106") (pintype "passive"))
    )
    (net (code "109") (name "/MOTOR_L4") (class "Default")
      (node (ref "D13") (pin "1") (pinfunction "A_1") (pintype "passive"))
      (node (ref "U4") (pin "102") (pinfunction "PE2_102") (pintype "passive"))
    )
    (net (code "110") (name "/MOTOR_L5") (class "Default")
      (node (ref "D16") (pin "1") (pinfunction "A_1") (pintype "passive"))
      (node (ref "U4") (pin "100") (pinfunction "PE4_100") (pintype "passive"))
    )
    (net (code "111") (name "/MOTOR_L6") (class "Default")
      (node (ref "D18") (pin "1") (pinfunction "A_1") (pintype "passive"))
      (node (ref "U4") (pin "98") (pinfunction "PE6_98") (pintype "passive"))
    )
    (net (code "112") (name "/MOTOR_L7") (class "Default")
      (node (ref "D21") (pin "1") (pinfunction "A_1") (pintype "passive"))
      (node (ref "U4") (pin "88") (pinfunction "PA15_88") (pintype "passive"))
    )
    (net (code "113") (name "/MOTOR_L8") (class "Default")
      (node (ref "D25") (pin "1") (pinfunction "A_1") (pintype "passive"))
      (node (ref "U4") (pin "62") (pinfunction "PE14_62") (pintype "passive"))
    )
    (net (code "114") (name "/MOTOR_L9") (class "Default")
      (node (ref "D28") (pin "1") (pinfunction "A_1") (pintype "passive"))
      (node (ref "U4") (pin "50") (pinfunction "PA7_50") (pintype "passive"))
    )
    (net (code "115") (name "/MOTOR_L10") (class "Default")
      (node (ref "D34") (pin "1") (pinfunction "A_1") (pintype "passive"))
      (node (ref "U4") (pin "44") (pinfunction "PE11_44") (pintype "passive"))
    )
    (net (code "116") (name "/MOTOR_PWR1") (class "Default")
      (node (ref "J5") (pin "10") (pinfunction "10_10") (pintype "passive"))
      (node (ref "U5") (pin "5") (pinfunction "D1_5") (pintype "passive"))
      (node (ref "U5") (pin "6") (pinfunction "D1_6") (pintype "passive"))
    )
    (net (code "117") (name "/MOTOR_PWR2") (class "Default")
      (node (ref "J5") (pin "9") (pinfunction "9_9") (pintype "passive"))
      (node (ref "U7") (pin "5") (pinfunction "D1_5") (pintype "passive"))
      (node (ref "U7") (pin "6") (pinfunction "D1_6") (pintype "passive"))
    )
    (net (code "118") (name "/MOTOR_PWR3") (class "Default")
      (node (ref "J5") (pin "8") (pinfunction "8_8") (pintype "passive"))
      (node (ref "U9") (pin "5") (pinfunction "D1_5") (pintype "passive"))
      (node (ref "U9") (pin "6") (pinfunction "D1_6") (pintype "passive"))
    )
    (net (code "119") (name "/MOTOR_PWR4") (class "Default")
      (node (ref "J5") (pin "7") (pinfunction "7_7") (pintype "passive"))
      (node (ref "U11") (pin "5") (pinfunction "D1_5") (pintype "passive"))
      (node (ref "U11") (pin "6") (pinfunction "D1_6") (pintype "passive"))
    )
    (net (code "120") (name "/MOTOR_PWR5") (class "Default")
      (node (ref "J5") (pin "6") (pinfunction "6_6") (pintype "passive"))
      (node (ref "U14") (pin "5") (pinfunction "D1_5") (pintype "passive"))
      (node (ref "U14") (pin "6") (pinfunction "D1_6") (pintype "passive"))
    )
    (net (code "121") (name "/MOTOR_PWR6") (class "Default")
      (node (ref "J5") (pin "5") (pinfunction "5_5") (pintype "passive"))
      (node (ref "U16") (pin "5") (pinfunction "D1_5") (pintype "passive"))
      (node (ref "U16") (pin "6") (pinfunction "D1_6") (pintype "passive"))
    )
    (net (code "122") (name "/MOTOR_PWR7") (class "Default")
      (node (ref "J5") (pin "4") (pinfunction "4_4") (pintype "passive"))
      (node (ref "U17") (pin "5") (pinfunction "D1_5") (pintype "passive"))
      (node (ref "U17") (pin "6") (pinfunction "D1_6") (pintype "passive"))
    )
    (net (code "123") (name "/MOTOR_PWR8") (class "Default")
      (node (ref "J5") (pin "3") (pinfunction "3_3") (pintype "passive"))
      (node (ref "U18") (pin "5") (pinfunction "D1_5") (pintype "passive"))
      (node (ref "U18") (pin "6") (pinfunction "D1_6") (pintype "passive"))
    )
    (net (code "124") (name "/MOTOR_PWR9") (class "Default")
      (node (ref "J5") (pin "2") (pinfunction "2_2") (pintype "passive"))
      (node (ref "U19") (pin "5") (pinfunction "D1_5") (pintype "passive"))
      (node (ref "U19") (pin "6") (pinfunction "D1_6") (pintype "passive"))
    )
    (net (code "125") (name "/MOTOR_PWR10") (class "Default")
      (node (ref "J5") (pin "1") (pinfunction "1_1") (pintype "passive"))
      (node (ref "U20") (pin "5") (pinfunction "D1_5") (pintype "passive"))
      (node (ref "U20") (pin "6") (pinfunction "D1_6") (pintype "passive"))
    )
    (net (code "126") (name "/MOTOR_R1") (class "Default")
      (node (ref "D8") (pin "1") (pinfunction "A_1") (pintype "passive"))
      (node (ref "U4") (pin "109") (pinfunction "PH10_109") (pintype "passive"))
    )
    (net (code "127") (name "/MOTOR_R2") (class "Default")
      (node (ref "D10") (pin "1") (pinfunction "A_1") (pintype "passive"))
      (node (ref "U4") (pin "107") (pinfunction "PH8_107") (pintype "passive"))
    )
    (net (code "128") (name "/MOTOR_R3") (class "Default")
      (node (ref "D12") (pin "1") (pinfunction "A_1") (pintype "passive"))
      (node (ref "U4") (pin "105") (pinfunction "PE1_105") (pintype "passive"))
    )
    (net (code "129") (name "/MOTOR_R4") (class "Default")
      (node (ref "D14") (pin "1") (pinfunction "A_1") (pintype "passive"))
      (node (ref "U4") (pin "101") (pinfunction "PE3_101") (pintype "passive"))
    )
    (net (code "130") (name "/MOTOR_R5") (class "Default")
      (node (ref "D17") (pin "1") (pinfunction "A_1") (pintype "passive"))
      (node (ref "U4") (pin "99") (pinfunction "PE5_99") (pintype "passive"))
    )
    (net (code "131") (name "/MOTOR_R6") (class "Default")
      (node (ref "D20") (pin "1") (pinfunction "A_1") (pintype "passive"))
      (node (ref "U4") (pin "97") (pinfunction "PE7_97") (pintype "passive"))
    )
    (net (code "132") (name "/MOTOR_R7") (class "Default")
      (node (ref "D22") (pin "1") (pinfunction "A_1") (pintype "passive"))
      (node (ref "U4") (pin "63") (pinfunction "PE15_63") (pintype "passive"))
    )
    (net (code "133") (name "/MOTOR_R8") (class "Default")
      (node (ref "D27") (pin "1") (pinfunction "A_1") (pintype "passive"))
      (node (ref "U4") (pin "51") (pinfunction "PA6_51") (pintype "passive"))
    )
    (net (code "134") (name "/MOTOR_R9") (class "Default")
      (node (ref "D32") (pin "1") (pinfunction "A_1") (pintype "passive"))
      (node (ref "U4") (pin "45") (pinfunction "PE12_45") (pintype "passive"))
    )
    (net (code "135") (name "/MOTOR_R10") (class "Default")
      (node (ref "D35") (pin "1") (pinfunction "A_1") (pintype "passive"))
      (node (ref "U4") (pin "43") (pinfunction "PE10_43") (pintype "passive"))
    )
    (net (code "136") (name "/MOTOR_S1") (class "Default")
      (node (ref "U4") (pin "128") (pinfunction "PB6/EADC0_CH6_128") (pintype "passive"))
    )
    (net (code "137") (name "/MOTOR_S2") (class "Default")
      (node (ref "U4") (pin "127") (pinfunction "PB7/EADC0_CH7_127") (pintype "passive"))
    )
    (net (code "138") (name "/MOTOR_S3") (class "Default")
      (node (ref "U4") (pin "126") (pinfunction "PB8/EADC0_CH8_126") (pintype "passive"))
    )
    (net (code "139") (name "/MOTOR_S4") (class "Default")
      (node (ref "U4") (pin "125") (pinfunction "PB9/EADC0_CH9_125") (pintype "passive"))
    )
    (net (code "140") (name "/MOTOR_S5") (class "Default")
      (node (ref "U4") (pin "124") (pinfunction "PB10/EADC0_CH10_124") (pintype "passive"))
    )
    (net (code "141") (name "/MOTOR_S6") (class "Default")
      (node (ref "U4") (pin "123") (pinfunction "PB11/EADC0_CH11_123") (pintype "passive"))
    )
    (net (code "142") (name "/MOTOR_S7") (class "Default")
      (node (ref "U4") (pin "119") (pinfunction "PB12/EADC0_CH12_119") (pintype "passive"))
    )
    (net (code "143") (name "/MOTOR_S8") (class "Default")
      (node (ref "U4") (pin "118") (pinfunction "PB13/EADC0_CH13_118") (pintype "passive"))
    )
    (net (code "144") (name "/MOTOR_S9") (class "Default")
      (node (ref "U4") (pin "117") (pinfunction "PB14/EADC0_CH14_117") (pintype "passive"))
    )
    (net (code "145") (name "/MOTOR_S10") (class "Default")
      (node (ref "U4") (pin "116") (pinfunction "PB15/EADC0_CH15_116") (pintype "passive"))
    )
    (net (code "146") (name "/MOTOR_S11") (class "Default")
      (node (ref "U4") (pin "115") (pinfunction "PC14_115") (pintype "passive"))
    )
    (net (code "147") (name "/MOTOR_S12") (class "Default")
      (node (ref "U4") (pin "111") (pinfunction "PD14_111") (pintype "passive"))
    )
    (net (code "148") (name "/NRST") (class "Default")
      (node (ref "C55") (pin "1") (pinfunction "1_1") (pintype "passive"))
      (node (ref "R82") (pin "1") (pinfunction "1_1") (pintype "passive"))
      (node (ref "S1") (pin "1") (pinfunction "1_1") (pintype "passive"))
      (node (ref "U4") (pin "64") (pinfunction "nREST_64") (pintype "passive"))
    )
    (net (code "149") (name "/R232_RX1") (class "Default")
      (node (ref "J10") (pin "3") (pinfunction "3_3") (pintype "passive"))
      (node (ref "U23") (pin "13") (pinfunction "R1in_13") (pintype "passive"))
    )
    (net (code "150") (name "/R232_RX2") (class "Default")
      (node (ref "J11") (pin "4") (pinfunction "4_4") (pintype "passive"))
      (node (ref "U23") (pin "8") (pinfunction "R2in_8") (pintype "passive"))
    )
    (net (code "151") (name "/R232_TX1") (class "Default")
      (node (ref "J10") (pin "2") (pinfunction "2_2") (pintype "passive"))
      (node (ref "U23") (pin "14") (pinfunction "T1out_14") (pintype "passive"))
    )
    (net (code "152") (name "/R232_TX2") (class "Default")
      (node (ref "J11") (pin "3") (pinfunction "3_3") (pintype "passive"))
      (node (ref "U23") (pin "7") (pinfunction "T2out_7") (pintype "passive"))
    )
    (net (code "153") (name "/SER") (class "Default")
      (node (ref "U15") (pin "14") (pinfunction "DS_14") (pintype "passive"))
      (node (ref "U4") (pin "4") (pinfunction "PB2/EADC0_CH2_4") (pintype "passive"))
    )
    (net (code "154") (name "/SET_BUTTON") (class "Default")
      (node (ref "R94") (pin "2") (pinfunction "2_2") (pintype "passive"))
      (node (ref "S2") (pin "1") (pinfunction "1_1") (pintype "passive"))
      (node (ref "U4") (pin "58") (pinfunction "PA2_58") (pintype "passive"))
    )
    (net (code "155") (name "/SHCP") (class "Default")
      (node (ref "U15") (pin "11") (pinfunction "SHCP_11") (pintype "passive"))
      (node (ref "U4") (pin "10") (pinfunction "PB0/EADC0_CH0_10") (pintype "passive"))
    )
    (net (code "156") (name "/STCP") (class "Default")
      (node (ref "U15") (pin "12") (pinfunction "STCP_12") (pintype "passive"))
      (node (ref "U4") (pin "9") (pinfunction "PB1/EADC0_CH1_9") (pintype "passive"))
    )
    (net (code "157") (name "/TEMP") (class "Default")
      (node (ref "R93") (pin "2") (pinfunction "2_2") (pintype "passive"))
      (node (ref "U21") (pin "7") (pinfunction "out2_7") (pintype "passive"))
      (node (ref "U4") (pin "1") (pinfunction "PB5/EADC0_CH5_1") (pintype "passive"))
    )
    (net (code "158") (name "/TEST_BUTTON") (class "Default")
      (node (ref "R101") (pin "2") (pinfunction "2_2") (pintype "passive"))
      (node (ref "S4") (pin "1") (pinfunction "1_1") (pintype "passive"))
      (node (ref "U4") (pin "59") (pinfunction "PA1_59") (pintype "passive"))
    )
    (net (code "159") (name "/USB_DM") (class "Default")
      (node (ref "P1") (pin "2") (pinfunction "UD-_2") (pintype "passive"))
      (node (ref "U4") (pin "86") (pinfunction "PA13/USB_D-_86") (pintype "passive"))
    )
    (net (code "160") (name "/USB_DP") (class "Default")
      (node (ref "P1") (pin "3") (pinfunction "UD+_3") (pintype "passive"))
      (node (ref "U4") (pin "87") (pinfunction "PA14/USB_D+_87") (pintype "passive"))
    )
    (net (code "161") (name "/VBAT") (class "Default")
      (node (ref "C51") (pin "1") (pinfunction "1_1") (pintype "passive"))
      (node (ref "D31") (pin "2") (pinfunction "K_2") (pintype "passive"))
      (node (ref "D33") (pin "2") (pinfunction "K_2") (pintype "passive"))
      (node (ref "U13") (pin "3") (pinfunction "VBAT_3") (pintype "passive"))
    )
    (net (code "162") (name "/VREF") (class "Default")
      (node (ref "C34") (pin "1") (pinfunction "1_1") (pintype "passive"))
      (node (ref "C35") (pin "1") (pinfunction "1_1") (pintype "passive"))
      (node (ref "C36") (pin "1") (pinfunction "1_1") (pintype "passive"))
      (node (ref "L2") (pin "2") (pinfunction "2_2") (pintype "passive"))
      (node (ref "U4") (pin "121") (pinfunction "VREF_121") (pintype "passive"))
    )
    (net (code "164") (name "/X32_IN") (class "Default")
      (node (ref "C52") (pin "2") (pinfunction "2_2") (pintype "passive"))
      (node (ref "U4") (pin "31") (pinfunction "PF5/X32_IN_31") (pintype "passive"))
      (node (ref "X1") (pin "2") (pinfunction "2_2") (pintype "passive"))
    )
    (net (code "165") (name "/X32_OUT") (class "Default")
      (node (ref "C53") (pin "1") (pinfunction "1_1") (pintype "passive"))
      (node (ref "U4") (pin "32") (pinfunction "PF4/X32_OUT_32") (pintype "passive"))
      (node (ref "X1") (pin "1") (pinfunction "1_1") (pintype "passive"))
    )
    (net (code "166") (name "/XT_IN") (class "Default")
      (node (ref "C54") (pin "2") (pinfunction "2_2") (pintype "passive"))
      (node (ref "R84") (pin "1") (pinfunction "1_1") (pintype "passive"))
      (node (ref "U4") (pin "37") (pinfunction "PF3/XT1_IN_37") (pintype "passive"))
      (node (ref "X2") (pin "1") (pinfunction "1_1") (pintype "passive"))
    )
    (net (code "167") (name "/XT_OUT") (class "Default")
      (node (ref "C56") (pin "1") (pinfunction "1_1") (pintype "passive"))
      (node (ref "R84") (pin "2") (pinfunction "2_2") (pintype "passive"))
      (node (ref "U4") (pin "38") (pinfunction "PF2/XT1_OUT_38") (pintype "passive"))
      (node (ref "X2") (pin "2") (pinfunction "2_2") (pintype "passive"))
    )
    (net (code "168") (name "3.5V") (class "Default")
      (node (ref "C17") (pin "2") (pinfunction "2_2") (pintype "passive"))
      (node (ref "C20") (pin "1") (pinfunction "1_1") (pintype "passive"))
      (node (ref "C21") (pin "1") (pinfunction "1_1") (pintype "passive"))
      (node (ref "C33") (pin "2") (pinfunction "2_2") (pintype "passive"))
      (node (ref "C40") (pin "1") (pinfunction "1_1") (pintype "passive"))
      (node (ref "C41") (pin "1") (pinfunction "1_1") (pintype "passive"))
      (node (ref "C42") (pin "1") (pinfunction "1_1") (pintype "passive"))
      (node (ref "C43") (pin "1") (pinfunction "1_1") (pintype "passive"))
      (node (ref "C50") (pin "1") (pinfunction "1_1") (pintype "passive"))
      (node (ref "C60") (pin "1") (pinfunction "1_1") (pintype "passive"))
      (node (ref "D31") (pin "1") (pinfunction "A_1") (pintype "passive"))
      (node (ref "J3") (pin "4") (pinfunction "4_4") (pintype "passive"))
      (node (ref "J6") (pin "4") (pinfunction "4_4") (pintype "passive"))
      (node (ref "L2") (pin "1") (pinfunction "1_1") (pintype "passive"))
      (node (ref "L3") (pin "1") (pinfunction "1_1") (pintype "passive"))
      (node (ref "Q27") (pin "2") (pinfunction "2_2") (pintype "passive"))
      (node (ref "Q28") (pin "2") (pinfunction "2_2") (pintype "passive"))
      (node (ref "Q29") (pin "2") (pinfunction "2_2") (pintype "passive"))
      (node (ref "Q30") (pin "2") (pinfunction "2_2") (pintype "passive"))
      (node (ref "R100") (pin "2") (pinfunction "2_2") (pintype "passive"))
      (node (ref "R101") (pin "1") (pinfunction "1_1") (pintype "passive"))
      (node (ref "R112") (pin "2") (pinfunction "2_2") (pintype "passive"))
      (node (ref "R113") (pin "2") (pinfunction "2_2") (pintype "passive"))
      (node (ref "R114") (pin "2") (pinfunction "2_2") (pintype "passive"))
      (node (ref "R115") (pin "2") (pinfunction "2_2") (pintype "passive"))
      (node (ref "R17") (pin "2") (pinfunction "2_2") (pintype "passive"))
      (node (ref "R24") (pin "1") (pinfunction "1_1") (pintype "passive"))
      (node (ref "R26") (pin "2") (pinfunction "2_2") (pintype "passive"))
      (node (ref "R56") (pin "2") (pinfunction "2_2") (pintype "passive"))
      (node (ref "R62") (pin "1") (pinfunction "1_1") (pintype "passive"))
      (node (ref "R63") (pin "1") (pinfunction "1_1") (pintype "passive"))
      (node (ref "R67") (pin "1") (pinfunction "1_1") (pintype "passive"))
      (node (ref "R70") (pin "2") (pinfunction "2_2") (pintype "passive"))
      (node (ref "R77") (pin "1") (pinfunction "1_1") (pintype "passive"))
      (node (ref "R82") (pin "2") (pinfunction "2_2") (pintype "passive"))
      (node (ref "R94") (pin "1") (pinfunction "1_1") (pintype "passive"))
      (node (ref "R96") (pin "1") (pinfunction "1_1") (pintype "passive"))
      (node (ref "U15") (pin "16") (pinfunction "VCC_16") (pintype "passive"))
      (node (ref "U22") (pin "1") (pinfunction "VCC_1") (pintype "passive"))
      (node (ref "U23") (pin "16") (pinfunction "VCC_16") (pintype "power_in"))
      (node (ref "U4") (pin "104") (pinfunction "VDD_104") (pintype "passive"))
      (node (ref "U4") (pin "114") (pinfunction "VDD_114") (pintype "passive"))
      (node (ref "U4") (pin "12") (pinfunction "VDD_12") (pintype "passive"))
      (node (ref "U4") (pin "30") (pinfunction "VDD_30") (pintype "passive"))
      (node (ref "U4") (pin "40") (pinfunction "VDD_40") (pintype "passive"))
      (node (ref "U4") (pin "53") (pinfunction "VDD_53") (pintype "passive"))
      (node (ref "U4") (pin "61") (pinfunction "VDDIO_61") (pintype "passive"))
      (node (ref "U4") (pin "76") (pinfunction "VDD_76") (pintype "passive"))
      (node (ref "U4") (pin "90") (pinfunction "VDD_90") (pintype "passive"))
      (node (ref "U6") (pin "8") (pinfunction "VCC_8") (pintype "passive"))
      (node (ref "U8") (pin "2") (pinfunction "Vout_2") (pintype "passive"))
      (node (ref "U8") (pin "4") (pinfunction "TAB_4") (pintype "passive"))
    )
    (net (code "169") (name "3V3") (class "Default")
      (node (ref "C23") (pin "1") (pinfunction "1_1") (pintype "passive"))
      (node (ref "C28") (pin "1") (pinfunction "1_1") (pintype "passive"))
      (node (ref "R35") (pin "2") (pinfunction "2_2") (pintype "passive"))
      (node (ref "R36") (pin "2") (pinfunction "2_2") (pintype "passive"))
      (node (ref "R45") (pin "2") (pinfunction "2_2") (pintype "passive"))
      (node (ref "R46") (pin "2") (pinfunction "2_2") (pintype "passive"))
      (node (ref "U10") (pin "8") (pinfunction "VDD_8") (pintype "passive"))
      (node (ref "U13") (pin "8") (pinfunction "VCC_8") (pintype "passive"))
    )
    (net (code "170") (name "5V") (class "Default")
      (node (ref "C18") (pin "1") (pinfunction "1_1") (pintype "passive"))
      (node (ref "C19") (pin "1") (pinfunction "1_1") (pintype "passive"))
      (node (ref "C29") (pin "1") (pinfunction "1_1") (pintype "passive"))
      (node (ref "C57") (pin "2") (pinfunction "2_2") (pintype "passive"))
      (node (ref "C58") (pin "1") (pinfunction "1_1") (pintype "passive"))
      (node (ref "D37") (pin "1") (pinfunction "1_1") (pintype "passive"))
      (node (ref "J11") (pin "1") (pinfunction "1_1") (pintype "passive"))
      (node (ref "J9") (pin "1") (pinfunction "1_1") (pintype "passive"))
      (node (ref "J9") (pin "10") (pinfunction "10_10") (pintype "passive"))
      (node (ref "L1") (pin "2") (pinfunction "2_2") (pintype "passive"))
      (node (ref "P1") (pin "1") (pinfunction "VCC_1") (pintype "passive"))
      (node (ref "R14") (pin "1") (pinfunction "1_1") (pintype "passive"))
      (node (ref "R23") (pin "1") (pinfunction "1_1") (pintype "passive"))
      (node (ref "R31") (pin "1") (pinfunction "1_1") (pintype "passive"))
      (node (ref "R38") (pin "1") (pinfunction "1_1") (pintype "passive"))
      (node (ref "R39") (pin "2") (pinfunction "2_2") (pintype "passive"))
      (node (ref "R48") (pin "1") (pinfunction "1_1") (pintype "passive"))
      (node (ref "R55") (pin "1") (pinfunction "1_1") (pintype "passive"))
      (node (ref "R61") (pin "1") (pinfunction "1_1") (pintype "passive"))
      (node (ref "R69") (pin "1") (pinfunction "1_1") (pintype "passive"))
      (node (ref "R78") (pin "1") (pinfunction "1_1") (pintype "passive"))
      (node (ref "R89") (pin "2") (pinfunction "2_2") (pintype "passive"))
      (node (ref "R9") (pin "1") (pinfunction "1_1") (pintype "passive"))
      (node (ref "R90") (pin "2") (pinfunction "2_2") (pintype "passive"))
      (node (ref "R95") (pin "2") (pinfunction "2_2") (pintype "passive"))
      (node (ref "R99") (pin "3") (pinfunction "3_3") (pintype "passive"))
      (node (ref "U21") (pin "8") (pinfunction "Vcc+_8") (pintype "passive"))
      (node (ref "U8") (pin "3") (pinfunction "Vin_3") (pintype "passive"))
    )
    (net (code "171") (name "24V") (class "Default")
      (node (ref "C25") (pin "1") (pinfunction "1_1") (pintype "passive"))
      (node (ref "C26") (pin "1") (pinfunction "1_1") (pintype "passive"))
      (node (ref "C27") (pin "1") (pinfunction "1_1") (pintype "passive"))
      (node (ref "D19") (pin "2") (pinfunction "K_2") (pintype "passive"))
      (node (ref "R11") (pin "1") (pinfunction "1_1") (pintype "passive"))
      (node (ref "R18") (pin "1") (pinfunction "1_1") (pintype "passive"))
      (node (ref "R27") (pin "1") (pinfunction "1_1") (pintype "passive"))
      (node (ref "R33") (pin "1") (pinfunction "1_1") (pintype "passive"))
      (node (ref "R41") (pin "1") (pinfunction "1_1") (pintype "passive"))
      (node (ref "R50") (pin "1") (pinfunction "1_1") (pintype "passive"))
      (node (ref "R58") (pin "1") (pinfunction "1_1") (pintype "passive"))
      (node (ref "R65") (pin "1") (pinfunction "1_1") (pintype "passive"))
      (node (ref "R73") (pin "1") (pinfunction "1_1") (pintype "passive"))
      (node (ref "R80") (pin "1") (pinfunction "1_1") (pintype "passive"))
      (node (ref "U11") (pin "3") (pinfunction "S1_3") (pintype "passive"))
      (node (ref "U12") (pin "2") (pinfunction "VIN_2") (pintype "passive"))
      (node (ref "U14") (pin "3") (pinfunction "S1_3") (pintype "passive"))
      (node (ref "U16") (pin "3") (pinfunction "S1_3") (pintype "passive"))
      (node (ref "U17") (pin "3") (pinfunction "S1_3") (pintype "passive"))
      (node (ref "U18") (pin "3") (pinfunction "S1_3") (pintype "passive"))
      (node (ref "U19") (pin "3") (pinfunction "S1_3") (pintype "passive"))
      (node (ref "U20") (pin "3") (pinfunction "S1_3") (pintype "passive"))
      (node (ref "U5") (pin "3") (pinfunction "S1_3") (pintype "passive"))
      (node (ref "U7") (pin "3") (pinfunction "S1_3") (pintype "passive"))
      (node (ref "U9") (pin "3") (pinfunction "S1_3") (pintype "passive"))
    )
    (net (code "172") (name "AGND") (class "Default")
      (node (ref "C25") (pin "2") (pinfunction "2_2") (pintype "passive"))
      (node (ref "D19") (pin "1") (pinfunction "1_1") (pintype "passive"))
      (node (ref "R52") (pin "1") (pinfunction "1_1") (pintype "passive"))
      (node (ref "R85") (pin "1") (pinfunction "1_1") (pintype "passive"))
    )
    (net (code "173") (name "GND") (class "Default")
      (node (ref "B1") (pin "2") (pinfunction "-_2") (pintype "passive"))
      (node (ref "C17") (pin "1") (pinfunction "1_1") (pintype "passive"))
      (node (ref "C18") (pin "2") (pinfunction "2_2") (pintype "passive"))
      (node (ref "C19") (pin "2") (pinfunction "2_2") (pintype "passive"))
      (node (ref "C20") (pin "2") (pinfunction "2_2") (pintype "passive"))
      (node (ref "C21") (pin "2") (pinfunction "2_2") (pintype "passive"))
      (node (ref "C22") (pin "2") (pinfunction "2_2") (pintype "passive"))
      (node (ref "C23") (pin "2") (pinfunction "2_2") (pintype "passive"))
      (node (ref "C26") (pin "2") (pinfunction "2_2") (pintype "passive"))
      (node (ref "C27") (pin "2") (pinfunction "2_2") (pintype "passive"))
      (node (ref "C28") (pin "2") (pinfunction "2_2") (pintype "passive"))
      (node (ref "C29") (pin "2") (pinfunction "2_2") (pintype "passive"))
      (node (ref "C30") (pin "2") (pinfunction "2_2") (pintype "passive"))
      (node (ref "C31") (pin "2") (pinfunction "2_2") (pintype "passive"))
      (node (ref "C32") (pin "2") (pinfunction "2_2") (pintype "passive"))
      (node (ref "C33") (pin "1") (pinfunction "1_1") (pintype "passive"))
      (node (ref "C40") (pin "2") (pinfunction "2_2") (pintype "passive"))
      (node (ref "C41") (pin "2") (pinfunction "2_2") (pintype "passive"))
      (node (ref "C42") (pin "2") (pinfunction "2_2") (pintype "passive"))
      (node (ref "C43") (pin "2") (pinfunction "2_2") (pintype "passive"))
      (node (ref "C44") (pin "2") (pinfunction "2_2") (pintype "passive"))
      (node (ref "C45") (pin "2") (pinfunction "2_2") (pintype "passive"))
      (node (ref "C46") (pin "2") (pinfunction "2_2") (pintype "passive"))
      (node (ref "C47") (pin "2") (pinfunction "2_2") (pintype "passive"))
      (node (ref "C48") (pin "2") (pinfunction "2_2") (pintype "passive"))
      (node (ref "C49") (pin "2") (pinfunction "2_2") (pintype "passive"))
      (node (ref "C50") (pin "2") (pinfunction "2_2") (pintype "passive"))
      (node (ref "C51") (pin "2") (pinfunction "2_2") (pintype "passive"))
      (node (ref "C52") (pin "1") (pinfunction "1_1") (pintype "passive"))
      (node (ref "C53") (pin "2") (pinfunction "2_2") (pintype "passive"))
      (node (ref "C54") (pin "1") (pinfunction "1_1") (pintype "passive"))
      (node (ref "C55") (pin "2") (pinfunction "2_2") (pintype "passive"))
      (node (ref "C56") (pin "2") (pinfunction "2_2") (pintype "passive"))
      (node (ref "C57") (pin "1") (pinfunction "1_1") (pintype "passive"))
      (node (ref "C58") (pin "2") (pinfunction "2_2") (pintype "passive"))
      (node (ref "C59") (pin "2") (pinfunction "2_2") (pintype "passive"))
      (node (ref "C63") (pin "2") (pinfunction "2_2") (pintype "passive"))
      (node (ref "D15") (pin "1") (pinfunction "A_1") (pintype "passive"))
      (node (ref "D26") (pin "2") (pinfunction "2_2") (pintype "passive"))
      (node (ref "D29") (pin "2") (pinfunction "K_2") (pintype "passive"))
      (node (ref "D30") (pin "2") (pinfunction "K_2") (pintype "passive"))
      (node (ref "D37") (pin "2") (pinfunction "K_2") (pintype "passive"))
      (node (ref "D40") (pin "2") (pinfunction "K_2") (pintype "passive"))
      (node (ref "D41") (pin "2") (pinfunction "K_2") (pintype "passive"))
      (node (ref "D42") (pin "2") (pinfunction "K_2") (pintype "passive"))
      (node (ref "D43") (pin "2") (pinfunction "K_2") (pintype "passive"))
      (node (ref "D44") (pin "2") (pinfunction "K_2") (pintype "passive"))
      (node (ref "D45") (pin "2") (pinfunction "K_2") (pintype "passive"))
      (node (ref "D46") (pin "2") (pinfunction "K_2") (pintype "passive"))
      (node (ref "D47") (pin "2") (pinfunction "K_2") (pintype "passive"))
      (node (ref "J10") (pin "1") (pinfunction "1_1") (pintype "passive"))
      (node (ref "J11") (pin "2") (pinfunction "2_2") (pintype "passive"))
      (node (ref "J6") (pin "1") (pinfunction "1_1") (pintype "passive"))
      (node (ref "J7") (pin "1") (pinfunction "1_1") (pintype "passive"))
      (node (ref "J9") (pin "11") (pinfunction "11_11") (pintype "passive"))
      (node (ref "J9") (pin "20") (pinfunction "20_20") (pintype "passive"))
      (node (ref "L4") (pin "1") (pinfunction "1_1") (pintype "passive"))
      (node (ref "P1") (pin "4") (pinfunction "GND_4") (pintype "passive"))
      (node (ref "Q10") (pin "2") (pinfunction "2_2") (pintype "passive"))
      (node (ref "Q11") (pin "2") (pinfunction "2_2") (pintype "passive"))
      (node (ref "Q12") (pin "2") (pinfunction "2_2") (pintype "passive"))
      (node (ref "Q13") (pin "2") (pinfunction "2_2") (pintype "passive"))
      (node (ref "Q14") (pin "2") (pinfunction "2_2") (pintype "passive"))
      (node (ref "Q15") (pin "2") (pinfunction "2_2") (pintype "passive"))
      (node (ref "Q16") (pin "2") (pinfunction "2_2") (pintype "passive"))
      (node (ref "Q17") (pin "2") (pinfunction "2_2") (pintype "passive"))
      (node (ref "Q18") (pin "2") (pinfunction "2_2") (pintype "passive"))
      (node (ref "Q19") (pin "2") (pinfunction "2_2") (pintype "passive"))
      (node (ref "Q20") (pin "2") (pinfunction "2_2") (pintype "passive"))
      (node (ref "Q21") (pin "2") (pinfunction "2_2") (pintype "passive"))
      (node (ref "Q22") (pin "2") (pinfunction "2_2") (pintype "passive"))
      (node (ref "Q23") (pin "2") (pinfunction "2_2") (pintype "passive"))
      (node (ref "Q24") (pin "2") (pinfunction "2_2") (pintype "passive"))
      (node (ref "Q25") (pin "2") (pinfunction "2_2") (pintype "passive"))
      (node (ref "Q26") (pin "2") (pinfunction "2_2") (pintype "passive"))
      (node (ref "Q31") (pin "2") (pinfunction "2_2") (pintype "passive"))
      (node (ref "Q32") (pin "2") (pinfunction "2_2") (pintype "passive"))
      (node (ref "Q33") (pin "2") (pinfunction "2_2") (pintype "passive"))
      (node (ref "Q34") (pin "2") (pinfunction "2_2") (pintype "passive"))
      (node (ref "Q4") (pin "2") (pinfunction "2_2") (pintype "passive"))
      (node (ref "Q5") (pin "2") (pinfunction "2_2") (pintype "passive"))
      (node (ref "Q6") (pin "2") (pinfunction "2_2") (pintype "passive"))
      (node (ref "Q7") (pin "2") (pinfunction "2_2") (pintype "passive"))
      (node (ref "Q8") (pin "2") (pinfunction "2_2") (pintype "passive"))
      (node (ref "Q9") (pin "2") (pinfunction "2_2") (pintype "passive"))
      (node (ref "R108") (pin "1") (pinfunction "1_1") (pintype "passive"))
      (node (ref "R109") (pin "1") (pinfunction "1_1") (pintype "passive"))
      (node (ref "R110") (pin "1") (pinfunction "1_1") (pintype "passive"))
      (node (ref "R111") (pin "1") (pinfunction "1_1") (pintype "passive"))
      (node (ref "R16") (pin "2") (pinfunction "2_2") (pintype "passive"))
      (node (ref "R29") (pin "1") (pinfunction "1_1") (pintype "passive"))
      (node (ref "R44") (pin "1") (pinfunction "1_1") (pintype "passive"))
      (node (ref "R52") (pin "2") (pinfunction "2_2") (pintype "passive"))
      (node (ref "R54") (pin "2") (pinfunction "2_2") (pintype "passive"))
      (node (ref "R71") (pin "2") (pinfunction "2_2") (pintype "passive"))
      (node (ref "R91") (pin "1") (pinfunction "1_1") (pintype "passive"))
      (node (ref "S1") (pin "2") (pinfunction "2_2") (pintype "passive"))
      (node (ref "S2") (pin "2") (pinfunction "2_2") (pintype "passive"))
      (node (ref "S3") (pin "2") (pinfunction "2_2") (pintype "passive"))
      (node (ref "S4") (pin "2") (pinfunction "2_2") (pintype "passive"))
      (node (ref "U10") (pin "1") (pinfunction "A0_1") (pintype "passive"))
      (node (ref "U10") (pin "2") (pinfunction "A1_2") (pintype "passive"))
      (node (ref "U10") (pin "3") (pinfunction "A2_3") (pintype "passive"))
      (node (ref "U10") (pin "4") (pinfunction "VSS_4") (pintype "passive"))
      (node (ref "U10") (pin "7") (pinfunction "WP_7") (pintype "passive"))
      (node (ref "U12") (pin "7") (pinfunction "GND_7") (pintype "passive"))
      (node (ref "U12") (pin "9") (pinfunction "PWP_9") (pintype "passive"))
      (node (ref "U13") (pin "4") (pinfunction "GND_4") (pintype "passive"))
      (node (ref "U13") (pin "7") (pinfunction "SQW/OUT_7") (pintype "passive"))
      (node (ref "U15") (pin "8") (pinfunction "GND_8") (pintype "passive"))
      (node (ref "U21") (pin "4") (pinfunction "Vcc-_4") (pintype "passive"))
      (node (ref "U23") (pin "15") (pinfunction "GND_15") (pintype "power_in"))
      (node (ref "U4") (pin "103") (pinfunction "VSS_103") (pintype "passive"))
      (node (ref "U4") (pin "11") (pinfunction "VSS_11") (pintype "passive"))
      (node (ref "U4") (pin "112") (pinfunction "VSS_112") (pintype "passive"))
      (node (ref "U4") (pin "39") (pinfunction "VSS_39") (pintype "passive"))
      (node (ref "U4") (pin "52") (pinfunction "VSS_52") (pintype "passive"))
      (node (ref "U4") (pin "75") (pinfunction "VSS_75") (pintype "passive"))
      (node (ref "U4") (pin "93") (pinfunction "VSS_93") (pintype "passive"))
      (node (ref "U6") (pin "5") (pinfunction "GND_5") (pintype "passive"))
    )
    (net (code "174") (name "Net-(B1-+)") (class "Default")
      (node (ref "B1") (pin "1") (pinfunction "+_1") (pintype "passive"))
      (node (ref "D33") (pin "1") (pinfunction "A_1") (pintype "passive"))
      (node (ref "R75") (pin "1") (pinfunction "1_1") (pintype "passive"))
    )
    (net (code "175") (name "Net-(C32-Pad1)") (class "Default")
      (node (ref "C32") (pin "1") (pinfunction "1_1") (pintype "passive"))
      (node (ref "R43") (pin "1") (pinfunction "1_1") (pintype "passive"))
    )
    (net (code "176") (name "Net-(D7-K)") (class "Default")
      (node (ref "D7") (pin "2") (pinfunction "K_2") (pintype "passive"))
      (node (ref "R10") (pin "1") (pinfunction "1_1") (pintype "passive"))
    )
    (net (code "177") (name "Net-(D8-K)") (class "Default")
      (node (ref "D8") (pin "2") (pinfunction "K_2") (pintype "passive"))
      (node (ref "R13") (pin "1") (pinfunction "1_1") (pintype "passive"))
    )
    (net (code "178") (name "Net-(D9-K)") (class "Default")
      (node (ref "D9") (pin "2") (pinfunction "K_2") (pintype "passive"))
      (node (ref "R15") (pin "1") (pinfunction "1_1") (pintype "passive"))
    )
    (net (code "179") (name "Net-(D10-K)") (class "Default")
      (node (ref "D10") (pin "2") (pinfunction "K_2") (pintype "passive"))
      (node (ref "R21") (pin "1") (pinfunction "1_1") (pintype "passive"))
    )
    (net (code "180") (name "Net-(D11-K)") (class "Default")
      (node (ref "D11") (pin "2") (pinfunction "K_2") (pintype "passive"))
      (node (ref "R25") (pin "1") (pinfunction "1_1") (pintype "passive"))
    )
    (net (code "181") (name "Net-(D12-K)") (class "Default")
      (node (ref "D12") (pin "2") (pinfunction "K_2") (pintype "passive"))
      (node (ref "R30") (pin "1") (pinfunction "1_1") (pintype "passive"))
    )
    (net (code "182") (name "Net-(D13-K)") (class "Default")
      (node (ref "D13") (pin "2") (pinfunction "K_2") (pintype "passive"))
      (node (ref "R32") (pin "1") (pinfunction "1_1") (pintype "passive"))
    )
    (net (code "183") (name "Net-(D14-K)") (class "Default")
      (node (ref "D14") (pin "2") (pinfunction "K_2") (pintype "passive"))
      (node (ref "R37") (pin "1") (pinfunction "1_1") (pintype "passive"))
    )
    (net (code "184") (name "Net-(D15-K)") (class "Default")
      (node (ref "C24") (pin "2") (pinfunction "2_2") (pintype "passive"))
      (node (ref "D15") (pin "2") (pinfunction "K_2") (pintype "passive"))
      (node (ref "L1") (pin "1") (pinfunction "1_1") (pintype "passive"))
      (node (ref "U12") (pin "8") (pinfunction "PH_8") (pintype "passive"))
    )
    (net (code "185") (name "Net-(D16-K)") (class "Default")
      (node (ref "D16") (pin "2") (pinfunction "K_2") (pintype "passive"))
      (node (ref "R40") (pin "1") (pinfunction "1_1") (pintype "passive"))
    )
    (net (code "186") (name "Net-(D17-K)") (class "Default")
      (node (ref "D17") (pin "2") (pinfunction "K_2") (pintype "passive"))
      (node (ref "R47") (pin "1") (pinfunction "1_1") (pintype "passive"))
    )
    (net (code "187") (name "Net-(D18-K)") (class "Default")
      (node (ref "D18") (pin "2") (pinfunction "K_2") (pintype "passive"))
      (node (ref "R49") (pin "1") (pinfunction "1_1") (pintype "passive"))
    )
    (net (code "188") (name "Net-(D20-K)") (class "Default")
      (node (ref "D20") (pin "2") (pinfunction "K_2") (pintype "passive"))
      (node (ref "R53") (pin "1") (pinfunction "1_1") (pintype "passive"))
    )
    (net (code "189") (name "Net-(D21-K)") (class "Default")
      (node (ref "D21") (pin "2") (pinfunction "K_2") (pintype "passive"))
      (node (ref "R57") (pin "1") (pinfunction "1_1") (pintype "passive"))
    )
    (net (code "190") (name "Net-(D22-K)") (class "Default")
      (node (ref "D22") (pin "2") (pinfunction "K_2") (pintype "passive"))
      (node (ref "R60") (pin "1") (pinfunction "1_1") (pintype "passive"))
    )
    (net (code "191") (name "Net-(D23-Pad1)") (class "Default")
      (node (ref "D23") (pin "1") (pinfunction "1_1") (pintype "passive"))
      (node (ref "R62") (pin "2") (pinfunction "2_2") (pintype "passive"))
    )
    (net (code "192") (name "Net-(D24-Pad1)") (class "Default")
      (node (ref "D24") (pin "1") (pinfunction "1_1") (pintype "passive"))
      (node (ref "R63") (pin "2") (pinfunction "2_2") (pintype "passive"))
    )
    (net (code "193") (name "Net-(D25-K)") (class "Default")
      (node (ref "D25") (pin "2") (pinfunction "K_2") (pintype "passive"))
      (node (ref "R64") (pin "1") (pinfunction "1_1") (pintype "passive"))
    )
    (net (code "194") (name "Net-(D26-Pad1)") (class "Default")
      (node (ref "D26") (pin "1") (pinfunction "1_1") (pintype "passive"))
      (node (ref "R67") (pin "2") (pinfunction "2_2") (pintype "passive"))
    )
    (net (code "195") (name "Net-(D27-K)") (class "Default")
      (node (ref "D27") (pin "2") (pinfunction "K_2") (pintype "passive"))
      (node (ref "R68") (pin "1") (pinfunction "1_1") (pintype "passive"))
    )
    (net (code "196") (name "Net-(D28-K)") (class "Default")
      (node (ref "D28") (pin "2") (pinfunction "K_2") (pintype "passive"))
      (node (ref "R72") (pin "1") (pinfunction "1_1") (pintype "passive"))
    )
    (net (code "197") (name "Net-(D32-K)") (class "Default")
      (node (ref "D32") (pin "2") (pinfunction "K_2") (pintype "passive"))
      (node (ref "R76") (pin "1") (pinfunction "1_1") (pintype "passive"))
    )
    (net (code "198") (name "Net-(D34-K)") (class "Default")
      (node (ref "D34") (pin "2") (pinfunction "K_2") (pintype "passive"))
      (node (ref "R79") (pin "1") (pinfunction "1_1") (pintype "passive"))
    )
    (net (code "199") (name "Net-(D35-K)") (class "Default")
      (node (ref "D35") (pin "2") (pinfunction "K_2") (pintype "passive"))
      (node (ref "R83") (pin "1") (pinfunction "1_1") (pintype "passive"))
    )
    (net (code "200") (name "Net-(D36-K)") (class "Default")
      (node (ref "D36") (pin "2") (pinfunction "K_2") (pintype "passive"))
      (node (ref "R85") (pin "2") (pinfunction "2_2") (pintype "passive"))
      (node (ref "U21") (pin "3") (pinfunction "In1+_3") (pintype "passive"))
    )
    (net (code "201") (name "Net-(D38-A)") (class "Default")
      (node (ref "D38") (pin "1") (pinfunction "A_1") (pintype "passive"))
      (node (ref "Q26") (pin "3") (pinfunction "3_3") (pintype "passive"))
      (node (ref "R95") (pin "1") (pinfunction "1_1") (pintype "passive"))
    )
    (net (code "202") (name "Net-(D39-K)") (class "Default")
      (node (ref "D39") (pin "2") (pinfunction "K_2") (pintype "passive"))
      (node (ref "R103") (pin "1") (pinfunction "1_1") (pintype "passive"))
    )
    (net (code "203") (name "Net-(J8-Pad2)") (class "Default")
      (node (ref "J8") (pin "2") (pinfunction "2_2") (pintype "passive"))
      (node (ref "R89") (pin "1") (pinfunction "1_1") (pintype "passive"))
    )
    (net (code "204") (name "Net-(J9-Pad9)") (class "Default")
      (node (ref "J9") (pin "9") (pinfunction "9_9") (pintype "passive"))
      (node (ref "R99") (pin "1") (pinfunction "1_1") (pintype "passive"))
    )
    (net (code "205") (name "Net-(Q4-Pad1)") (class "Default")
      (node (ref "Q4") (pin "1") (pinfunction "1_1") (pintype "passive"))
      (node (ref "R10") (pin "2") (pinfunction "2_2") (pintype "passive"))
    )
    (net (code "206") (name "Net-(Q5-Pad1)") (class "Default")
      (node (ref "Q5") (pin "1") (pinfunction "1_1") (pintype "passive"))
      (node (ref "R13") (pin "2") (pinfunction "2_2") (pintype "passive"))
    )
    (net (code "207") (name "Net-(Q5-Pad3)") (class "Default")
      (node (ref "Q5") (pin "3") (pinfunction "3_3") (pintype "passive"))
      (node (ref "R12") (pin "2") (pinfunction "2_2") (pintype "passive"))
    )
    (net (code "208") (name "Net-(Q6-Pad1)") (class "Default")
      (node (ref "Q6") (pin "1") (pinfunction "1_1") (pintype "passive"))
      (node (ref "R15") (pin "2") (pinfunction "2_2") (pintype "passive"))
    )
    (net (code "209") (name "Net-(Q7-Pad1)") (class "Default")
      (node (ref "Q7") (pin "1") (pinfunction "1_1") (pintype "passive"))
      (node (ref "R21") (pin "2") (pinfunction "2_2") (pintype "passive"))
    )
    (net (code "210") (name "Net-(Q7-Pad3)") (class "Default")
      (node (ref "Q7") (pin "3") (pinfunction "3_3") (pintype "passive"))
      (node (ref "R19") (pin "2") (pinfunction "2_2") (pintype "passive"))
    )
    (net (code "211") (name "Net-(Q8-Pad1)") (class "Default")
      (node (ref "Q8") (pin "1") (pinfunction "1_1") (pintype "passive"))
      (node (ref "R22") (pin "2") (pinfunction "2_2") (pintype "passive"))
    )
    (net (code "212") (name "Net-(Q9-Pad1)") (class "Default")
      (node (ref "Q9") (pin "1") (pinfunction "1_1") (pintype "passive"))
      (node (ref "R25") (pin "2") (pinfunction "2_2") (pintype "passive"))
    )
    (net (code "213") (name "Net-(Q10-Pad1)") (class "Default")
      (node (ref "Q10") (pin "1") (pinfunction "1_1") (pintype "passive"))
      (node (ref "R30") (pin "2") (pinfunction "2_2") (pintype "passive"))
    )
    (net (code "214") (name "Net-(Q10-Pad3)") (class "Default")
      (node (ref "Q10") (pin "3") (pinfunction "3_3") (pintype "passive"))
      (node (ref "R28") (pin "2") (pinfunction "2_2") (pintype "passive"))
    )
    (net (code "215") (name "Net-(Q11-Pad1)") (class "Default")
      (node (ref "Q11") (pin "1") (pinfunction "1_1") (pintype "passive"))
      (node (ref "R32") (pin "2") (pinfunction "2_2") (pintype "passive"))
    )
    (net (code "216") (name "Net-(Q12-Pad1)") (class "Default")
      (node (ref "Q12") (pin "1") (pinfunction "1_1") (pintype "passive"))
      (node (ref "R37") (pin "2") (pinfunction "2_2") (pintype "passive"))
    )
    (net (code "217") (name "Net-(Q12-Pad3)") (class "Default")
      (node (ref "Q12") (pin "3") (pinfunction "3_3") (pintype "passive"))
      (node (ref "R34") (pin "2") (pinfunction "2_2") (pintype "passive"))
    )
    (net (code "218") (name "Net-(Q13-Pad1)") (class "Default")
      (node (ref "Q13") (pin "1") (pinfunction "1_1") (pintype "passive"))
      (node (ref "R40") (pin "2") (pinfunction "2_2") (pintype "passive"))
    )
    (net (code "219") (name "Net-(Q14-Pad1)") (class "Default")
      (node (ref "Q14") (pin "1") (pinfunction "1_1") (pintype "passive"))
      (node (ref "R47") (pin "2") (pinfunction "2_2") (pintype "passive"))
    )
    (net (code "220") (name "Net-(Q14-Pad3)") (class "Default")
      (node (ref "Q14") (pin "3") (pinfunction "3_3") (pintype "passive"))
      (node (ref "R42") (pin "2") (pinfunction "2_2") (pintype "passive"))
    )
    (net (code "221") (name "Net-(Q15-Pad1)") (class "Default")
      (node (ref "Q15") (pin "1") (pinfunction "1_1") (pintype "passive"))
      (node (ref "R49") (pin "2") (pinfunction "2_2") (pintype "passive"))
    )
    (net (code "222") (name "Net-(Q16-Pad1)") (class "Default")
      (node (ref "Q16") (pin "1") (pinfunction "1_1") (pintype "passive"))
      (node (ref "R53") (pin "2") (pinfunction "2_2") (pintype "passive"))
    )
    (net (code "223") (name "Net-(Q16-Pad3)") (class "Default")
      (node (ref "Q16") (pin "3") (pinfunction "3_3") (pintype "passive"))
      (node (ref "R51") (pin "2") (pinfunction "2_2") (pintype "passive"))
    )
    (net (code "224") (name "Net-(Q17-Pad1)") (class "Default")
      (node (ref "Q17") (pin "1") (pinfunction "1_1") (pintype "passive"))
      (node (ref "R57") (pin "2") (pinfunction "2_2") (pintype "passive"))
    )
    (net (code "225") (name "Net-(Q18-Pad1)") (class "Default")
      (node (ref "Q18") (pin "1") (pinfunction "1_1") (pintype "passive"))
      (node (ref "R60") (pin "2") (pinfunction "2_2") (pintype "passive"))
    )
    (net (code "226") (name "Net-(Q18-Pad3)") (class "Default")
      (node (ref "Q18") (pin "3") (pinfunction "3_3") (pintype "passive"))
      (node (ref "R59") (pin "2") (pinfunction "2_2") (pintype "passive"))
    )
    (net (code "227") (name "Net-(Q19-Pad1)") (class "Default")
      (node (ref "Q19") (pin "1") (pinfunction "1_1") (pintype "passive"))
      (node (ref "R64") (pin "2") (pinfunction "2_2") (pintype "passive"))
    )
    (net (code "228") (name "Net-(Q20-Pad1)") (class "Default")
      (node (ref "Q20") (pin "1") (pinfunction "1_1") (pintype "passive"))
      (node (ref "R68") (pin "2") (pinfunction "2_2") (pintype "passive"))
    )
    (net (code "229") (name "Net-(Q20-Pad3)") (class "Default")
      (node (ref "Q20") (pin "3") (pinfunction "3_3") (pintype "passive"))
      (node (ref "R66") (pin "2") (pinfunction "2_2") (pintype "passive"))
    )
    (net (code "230") (name "Net-(Q21-Pad1)") (class "Default")
      (node (ref "Q21") (pin "1") (pinfunction "1_1") (pintype "passive"))
      (node (ref "R72") (pin "2") (pinfunction "2_2") (pintype "passive"))
    )
    (net (code "231") (name "Net-(Q22-Pad1)") (class "Default")
      (node (ref "Q22") (pin "1") (pinfunction "1_1") (pintype "passive"))
      (node (ref "R76") (pin "2") (pinfunction "2_2") (pintype "passive"))
    )
    (net (code "232") (name "Net-(Q22-Pad3)") (class "Default")
      (node (ref "Q22") (pin "3") (pinfunction "3_3") (pintype "passive"))
      (node (ref "R74") (pin "2") (pinfunction "2_2") (pintype "passive"))
    )
    (net (code "233") (name "Net-(Q23-Pad1)") (class "Default")
      (node (ref "Q23") (pin "1") (pinfunction "1_1") (pintype "passive"))
      (node (ref "R79") (pin "2") (pinfunction "2_2") (pintype "passive"))
    )
    (net (code "234") (name "Net-(Q24-Pad1)") (class "Default")
      (node (ref "Q24") (pin "1") (pinfunction "1_1") (pintype "passive"))
      (node (ref "R83") (pin "2") (pinfunction "2_2") (pintype "passive"))
    )
    (net (code "235") (name "Net-(Q24-Pad3)") (class "Default")
      (node (ref "Q24") (pin "3") (pinfunction "3_3") (pintype "passive"))
      (node (ref "R81") (pin "2") (pinfunction "2_2") (pintype "passive"))
    )
    (net (code "236") (name "Net-(Q25-Pad1)") (class "Default")
      (node (ref "Q25") (pin "1") (pinfunction "1_1") (pintype "passive"))
      (node (ref "R98") (pin "2") (pinfunction "2_2") (pintype "passive"))
    )
    (net (code "237") (name "Net-(Q26-Pad1)") (class "Default")
      (node (ref "Q26") (pin "1") (pinfunction "1_1") (pintype "passive"))
      (node (ref "R102") (pin "2") (pinfunction "2_2") (pintype "passive"))
    )
    (net (code "238") (name "Net-(Q27-Pad1)") (class "Default")
      (node (ref "Q27") (pin "1") (pinfunction "1_1") (pintype "passive"))
      (node (ref "R104") (pin "2") (pinfunction "2_2") (pintype "passive"))
    )
    (net (code "239") (name "Net-(Q28-Pad1)") (class "Default")
      (node (ref "Q28") (pin "1") (pinfunction "1_1") (pintype "passive"))
      (node (ref "R105") (pin "2") (pinfunction "2_2") (pintype "passive"))
    )
    (net (code "240") (name "Net-(Q29-Pad1)") (class "Default")
      (node (ref "Q29") (pin "1") (pinfunction "1_1") (pintype "passive"))
      (node (ref "R106") (pin "2") (pinfunction "2_2") (pintype "passive"))
    )
    (net (code "241") (name "Net-(Q30-Pad1)") (class "Default")
      (node (ref "Q30") (pin "1") (pinfunction "1_1") (pintype "passive"))
      (node (ref "R107") (pin "2") (pinfunction "2_2") (pintype "passive"))
    )
    (net (code "242") (name "Net-(Q31-Pad1)") (class "Default")
      (node (ref "Q31") (pin "1") (pinfunction "1_1") (pintype "passive"))
      (node (ref "R116") (pin "2") (pinfunction "2_2") (pintype "passive"))
    )
    (net (code "243") (name "Net-(Q32-Pad1)") (class "Default")
      (node (ref "Q32") (pin "1") (pinfunction "1_1") (pintype "passive"))
      (node (ref "R117") (pin "2") (pinfunction "2_2") (pintype "passive"))
    )
    (net (code "244") (name "Net-(Q33-Pad1)") (class "Default")
      (node (ref "Q33") (pin "1") (pinfunction "1_1") (pintype "passive"))
      (node (ref "R118") (pin "2") (pinfunction "2_2") (pintype "passive"))
    )
    (net (code "245") (name "Net-(Q34-Pad1)") (class "Default")
      (node (ref "Q34") (pin "1") (pinfunction "1_1") (pintype "passive"))
      (node (ref "R119") (pin "2") (pinfunction "2_2") (pintype "passive"))
    )
    (net (code "246") (name "Net-(R99-W)") (class "Default")
      (node (ref "J9") (pin "12") (pinfunction "12_12") (pintype "passive"))
      (node (ref "R99") (pin "2") (pinfunction "W_2") (pintype "passive"))
    )
    (net (code "247") (name "Net-(U5-G1)") (class "Default")
      (node (ref "R11") (pin "2") (pinfunction "2_2") (pintype "passive"))
      (node (ref "R12") (pin "1") (pinfunction "1_1") (pintype "passive"))
      (node (ref "U5") (pin "4") (pinfunction "G1_4") (pintype "passive"))
    )
    (net (code "248") (name "Net-(U5-G2)") (class "Default")
      (node (ref "Q4") (pin "3") (pinfunction "3_3") (pintype "passive"))
      (node (ref "R9") (pin "2") (pinfunction "2_2") (pintype "passive"))
      (node (ref "U5") (pin "2") (pinfunction "G2_2") (pintype "passive"))
    )
    (net (code "249") (name "Net-(U6-DE)") (class "Default")
      (node (ref "Q8") (pin "3") (pinfunction "3_3") (pintype "passive"))
      (node (ref "R17") (pin "1") (pinfunction "1_1") (pintype "passive"))
      (node (ref "U6") (pin "2") (pinfunction "~{RE}_2") (pintype "passive"))
      (node (ref "U6") (pin "3") (pinfunction "DE_3") (pintype "passive"))
    )
    (net (code "250") (name "Net-(U7-G1)") (class "Default")
      (node (ref "R18") (pin "2") (pinfunction "2_2") (pintype "passive"))
      (node (ref "R19") (pin "1") (pinfunction "1_1") (pintype "passive"))
      (node (ref "U7") (pin "4") (pinfunction "G1_4") (pintype "passive"))
    )
    (net (code "251") (name "Net-(U7-G2)") (class "Default")
      (node (ref "Q6") (pin "3") (pinfunction "3_3") (pintype "passive"))
      (node (ref "R14") (pin "2") (pinfunction "2_2") (pintype "passive"))
      (node (ref "U7") (pin "2") (pinfunction "G2_2") (pintype "passive"))
    )
    (net (code "252") (name "Net-(U8-ADJ)") (class "Default")
      (node (ref "C22") (pin "1") (pinfunction "1_1") (pintype "passive"))
      (node (ref "R26") (pin "1") (pinfunction "1_1") (pintype "passive"))
      (node (ref "R29") (pin "2") (pinfunction "2_2") (pintype "passive"))
      (node (ref "U8") (pin "1") (pinfunction "ADJ_1") (pintype "passive"))
    )
    (net (code "253") (name "Net-(U9-G1)") (class "Default")
      (node (ref "R27") (pin "2") (pinfunction "2_2") (pintype "passive"))
      (node (ref "R28") (pin "1") (pinfunction "1_1") (pintype "passive"))
      (node (ref "U9") (pin "4") (pinfunction "G1_4") (pintype "passive"))
    )
    (net (code "254") (name "Net-(U9-G2)") (class "Default")
      (node (ref "Q9") (pin "3") (pinfunction "3_3") (pintype "passive"))
      (node (ref "R23") (pin "2") (pinfunction "2_2") (pintype "passive"))
      (node (ref "U9") (pin "2") (pinfunction "G2_2") (pintype "passive"))
    )
    (net (code "255") (name "Net-(U11-G1)") (class "Default")
      (node (ref "R33") (pin "2") (pinfunction "2_2") (pintype "passive"))
      (node (ref "R34") (pin "1") (pinfunction "1_1") (pintype "passive"))
      (node (ref "U11") (pin "4") (pinfunction "G1_4") (pintype "passive"))
    )
    (net (code "256") (name "Net-(U11-G2)") (class "Default")
      (node (ref "Q11") (pin "3") (pinfunction "3_3") (pintype "passive"))
      (node (ref "R31") (pin "2") (pinfunction "2_2") (pintype "passive"))
      (node (ref "U11") (pin "2") (pinfunction "G2_2") (pintype "passive"))
    )
    (net (code "257") (name "Net-(U11-S2)") (class "Default")
      (node (ref "D36") (pin "1") (pinfunction "1_1") (pintype "passive"))
      (node (ref "U11") (pin "1") (pinfunction "S2_1") (pintype "passive"))
      (node (ref "U14") (pin "1") (pinfunction "S2_1") (pintype "passive"))
      (node (ref "U16") (pin "1") (pinfunction "S2_1") (pintype "passive"))
      (node (ref "U17") (pin "1") (pinfunction "S2_1") (pintype "passive"))
      (node (ref "U18") (pin "1") (pinfunction "S2_1") (pintype "passive"))
      (node (ref "U19") (pin "1") (pinfunction "S2_1") (pintype "passive"))
      (node (ref "U20") (pin "1") (pinfunction "S2_1") (pintype "passive"))
      (node (ref "U5") (pin "1") (pinfunction "S2_1") (pintype "passive"))
      (node (ref "U7") (pin "1") (pinfunction "S2_1") (pintype "passive"))
      (node (ref "U9") (pin "1") (pinfunction "S2_1") (pintype "passive"))
    )
    (net (code "258") (name "Net-(U12-BOOT)") (class "Default")
      (node (ref "C24") (pin "1") (pinfunction "1_1") (pintype "passive"))
      (node (ref "U12") (pin "1") (pinfunction "BOOT_1") (pintype "passive"))
    )
    (net (code "259") (name "Net-(U12-COMP)") (class "Default")
      (node (ref "C31") (pin "1") (pinfunction "1_1") (pintype "passive"))
      (node (ref "R43") (pin "2") (pinfunction "2_2") (pintype "passive"))
      (node (ref "U12") (pin "6") (pinfunction "COMP_6") (pintype "passive"))
    )
    (net (code "260") (name "Net-(U12-SS)") (class "Default")
      (node (ref "C30") (pin "1") (pinfunction "1_1") (pintype "passive"))
      (node (ref "U12") (pin "4") (pinfunction "SS_4") (pintype "passive"))
    )
    (net (code "261") (name "Net-(U12-VSENSE)") (class "Default")
      (node (ref "R39") (pin "1") (pinfunction "1_1") (pintype "passive"))
      (node (ref "R44") (pin "2") (pinfunction "2_2") (pintype "passive"))
      (node (ref "U12") (pin "5") (pinfunction "VSENSE_5") (pintype "passive"))
    )
    (net (code "262") (name "Net-(U14-G1)") (class "Default")
      (node (ref "R41") (pin "2") (pinfunction "2_2") (pintype "passive"))
      (node (ref "R42") (pin "1") (pinfunction "1_1") (pintype "passive"))
      (node (ref "U14") (pin "4") (pinfunction "G1_4") (pintype "passive"))
    )
    (net (code "263") (name "Net-(U14-G2)") (class "Default")
      (node (ref "Q13") (pin "3") (pinfunction "3_3") (pintype "passive"))
      (node (ref "R38") (pin "2") (pinfunction "2_2") (pintype "passive"))
      (node (ref "U14") (pin "2") (pinfunction "G2_2") (pintype "passive"))
    )
    (net (code "264") (name "Net-(U15-~{MR})") (class "Default")
      (node (ref "R56") (pin "1") (pinfunction "1_1") (pintype "passive"))
      (node (ref "U15") (pin "10") (pinfunction "~{MR}_10") (pintype "passive"))
    )
    (net (code "265") (name "Net-(U15-~{OE})") (class "Default")
      (node (ref "R54") (pin "1") (pinfunction "1_1") (pintype "passive"))
      (node (ref "U15") (pin "13") (pinfunction "~{OE}_13") (pintype "passive"))
    )
    (net (code "266") (name "Net-(U16-G1)") (class "Default")
      (node (ref "R50") (pin "2") (pinfunction "2_2") (pintype "passive"))
      (node (ref "R51") (pin "1") (pinfunction "1_1") (pintype "passive"))
      (node (ref "U16") (pin "4") (pinfunction "G1_4") (pintype "passive"))
    )
    (net (code "267") (name "Net-(U16-G2)") (class "Default")
      (node (ref "Q15") (pin "3") (pinfunction "3_3") (pintype "passive"))
      (node (ref "R48") (pin "2") (pinfunction "2_2") (pintype "passive"))
      (node (ref "U16") (pin "2") (pinfunction "G2_2") (pintype "passive"))
    )
    (net (code "268") (name "Net-(U17-G1)") (class "Default")
      (node (ref "R58") (pin "2") (pinfunction "2_2") (pintype "passive"))
      (node (ref "R59") (pin "1") (pinfunction "1_1") (pintype "passive"))
      (node (ref "U17") (pin "4") (pinfunction "G1_4") (pintype "passive"))
    )
    (net (code "269") (name "Net-(U17-G2)") (class "Default")
      (node (ref "Q17") (pin "3") (pinfunction "3_3") (pintype "passive"))
      (node (ref "R55") (pin "2") (pinfunction "2_2") (pintype "passive"))
      (node (ref "U17") (pin "2") (pinfunction "G2_2") (pintype "passive"))
    )
    (net (code "270") (name "Net-(U18-G1)") (class "Default")
      (node (ref "R65") (pin "2") (pinfunction "2_2") (pintype "passive"))
      (node (ref "R66") (pin "1") (pinfunction "1_1") (pintype "passive"))
      (node (ref "U18") (pin "4") (pinfunction "G1_4") (pintype "passive"))
    )
    (net (code "271") (name "Net-(U18-G2)") (class "Default")
      (node (ref "Q19") (pin "3") (pinfunction "3_3") (pintype "passive"))
      (node (ref "R61") (pin "2") (pinfunction "2_2") (pintype "passive"))
      (node (ref "U18") (pin "2") (pinfunction "G2_2") (pintype "passive"))
    )
    (net (code "272") (name "Net-(U19-G1)") (class "Default")
      (node (ref "R73") (pin "2") (pinfunction "2_2") (pintype "passive"))
      (node (ref "R74") (pin "1") (pinfunction "1_1") (pintype "passive"))
      (node (ref "U19") (pin "4") (pinfunction "G1_4") (pintype "passive"))
    )
    (net (code "273") (name "Net-(U19-G2)") (class "Default")
      (node (ref "Q21") (pin "3") (pinfunction "3_3") (pintype "passive"))
      (node (ref "R69") (pin "2") (pinfunction "2_2") (pintype "passive"))
      (node (ref "U19") (pin "2") (pinfunction "G2_2") (pintype "passive"))
    )
    (net (code "274") (name "Net-(U20-G1)") (class "Default")
      (node (ref "R80") (pin "2") (pinfunction "2_2") (pintype "passive"))
      (node (ref "R81") (pin "1") (pinfunction "1_1") (pintype "passive"))
      (node (ref "U20") (pin "4") (pinfunction "G1_4") (pintype "passive"))
    )
    (net (code "275") (name "Net-(U20-G2)") (class "Default")
      (node (ref "Q23") (pin "3") (pinfunction "3_3") (pintype "passive"))
      (node (ref "R78") (pin "2") (pinfunction "2_2") (pintype "passive"))
      (node (ref "U20") (pin "2") (pinfunction "G2_2") (pintype "passive"))
    )
    (net (code "276") (name "Net-(U21A-In1-)") (class "Default")
      (node (ref "R86") (pin "1") (pinfunction "1_1") (pintype "passive"))
      (node (ref "U21") (pin "2") (pinfunction "In1-_2") (pintype "passive"))
    )
    (net (code "277") (name "Net-(U21B-In2+)") (class "Default")
      (node (ref "J8") (pin "1") (pinfunction "1_1") (pintype "passive"))
      (node (ref "R91") (pin "2") (pinfunction "2_2") (pintype "passive"))
      (node (ref "U21") (pin "5") (pinfunction "In2+_5") (pintype "passive"))
    )
    (net (code "278") (name "Net-(U21B-In2-)") (class "Default")
      (node (ref "R93") (pin "1") (pinfunction "1_1") (pintype "passive"))
      (node (ref "U21") (pin "6") (pinfunction "In2-_6") (pintype "passive"))
    )
    (net (code "279") (name "Net-(U22-B)") (class "Default")
      (node (ref "Q25") (pin "3") (pinfunction "3_3") (pintype "passive"))
      (node (ref "U22") (pin "2") (pinfunction "B_2") (pintype "passive"))
    )
    (net (code "280") (name "Net-(U23-C1+)") (class "Default")
      (node (ref "C61") (pin "1") (pinfunction "1_1") (pintype "passive"))
      (node (ref "U23") (pin "1") (pinfunction "C1+_1") (pintype "passive"))
    )
    (net (code "281") (name "Net-(U23-C1-)") (class "Default")
      (node (ref "C61") (pin "2") (pinfunction "2_2") (pintype "passive"))
      (node (ref "U23") (pin "3") (pinfunction "C1-_3") (pintype "passive"))
    )
    (net (code "282") (name "Net-(U23-C2+)") (class "Default")
      (node (ref "C62") (pin "2") (pinfunction "2_2") (pintype "passive"))
      (node (ref "U23") (pin "4") (pinfunction "C2+_4") (pintype "passive"))
    )
    (net (code "283") (name "Net-(U23-C2-)") (class "Default")
      (node (ref "C62") (pin "1") (pinfunction "1_1") (pintype "passive"))
      (node (ref "U23") (pin "5") (pinfunction "C2-_5") (pintype "passive"))
    )
    (net (code "284") (name "Net-(U23-V+)") (class "Default")
      (node (ref "C60") (pin "2") (pinfunction "2_2") (pintype "passive"))
      (node (ref "U23") (pin "2") (pinfunction "V+_2") (pintype "passive"))
    )
    (net (code "285") (name "Net-(U23-V-)") (class "Default")
      (node (ref "C63") (pin "1") (pinfunction "1_1") (pintype "passive"))
      (node (ref "U23") (pin "6") (pinfunction "V-_6") (pintype "passive"))
    )
    (net (code "286") (name "unconnected-(J9-Pad18)") (class "Default")
      (node (ref "J9") (pin "18") (pinfunction "18_18") (pintype "passive"))
    )
    (net (code "287") (name "unconnected-(R87-Pad3)") (class "Default")
      (node (ref "R87") (pin "3") (pinfunction "3_3") (pintype "passive"))
    )
    (net (code "288") (name "unconnected-(R87-Pad4)") (class "Default")
      (node (ref "R87") (pin "4") (pinfunction "4_4") (pintype "passive"))
    )
    (net (code "289") (name "unconnected-(R87-Pad5)") (class "Default")
      (node (ref "R87") (pin "5") (pinfunction "5_5") (pintype "passive"))
    )
    (net (code "290") (name "unconnected-(R87-Pad6)") (class "Default")
      (node (ref "R87") (pin "6") (pinfunction "6_6") (pintype "passive"))
    )
    (net (code "291") (name "unconnected-(R97-Pad3)") (class "Default")
      (node (ref "R97") (pin "3") (pinfunction "3_3") (pintype "passive"))
    )
    (net (code "292") (name "unconnected-(R97-Pad6)") (class "Default")
      (node (ref "R97") (pin "6") (pinfunction "6_6") (pintype "passive"))
    )
    (net (code "293") (name "unconnected-(U4-NC-Pad89)") (class "Default")
      (node (ref "U4") (pin "89") (pinfunction "NC_89") (pintype "passive"))
    )
    (net (code "294") (name "unconnected-(U4-NC-Pad91)") (class "Default")
      (node (ref "U4") (pin "91") (pinfunction "NC_91") (pintype "passive"))
    )
    (net (code "295") (name "unconnected-(U4-NC-Pad92)") (class "Default")
      (node (ref "U4") (pin "92") (pinfunction "NC_92") (pintype "passive"))
    )
    (net (code "296") (name "unconnected-(U4-NC-Pad94)") (class "Default")
      (node (ref "U4") (pin "94") (pinfunction "NC_94") (pintype "passive"))
    )
    (net (code "297") (name "unconnected-(U4-NC-Pad96)") (class "Default")
      (node (ref "U4") (pin "96") (pinfunction "NC_96") (pintype "passive"))
    )
    (net (code "298") (name "unconnected-(U4-PG4-Pad23)") (class "Default")
      (node (ref "U4") (pin "23") (pinfunction "PG4_23") (pintype "passive"))
    )
    (net (code "299") (name "unconnected-(U12-EN-Pad3)") (class "Default")
      (node (ref "U12") (pin "3") (pinfunction "EN_3") (pintype "passive"))
    )
    (net (code "300") (name "unconnected-(U13-X1-Pad1)") (class "Default")
      (node (ref "U13") (pin "1") (pinfunction "X1_1") (pintype "passive"))
    )
    (net (code "301") (name "unconnected-(U13-X2-Pad2)") (class "Default")
      (node (ref "U13") (pin "2") (pinfunction "X2_2") (pintype "passive"))
    )
    (net (code "302") (name "unconnected-(U15-Q7S-Pad9)") (class "Default")
      (node (ref "U15") (pin "9") (pinfunction "Q7S_9") (pintype "passive"))
    )
  )
)
